# bldc_controller.net
KiCad netlist of a schematic drawn in EAGLE
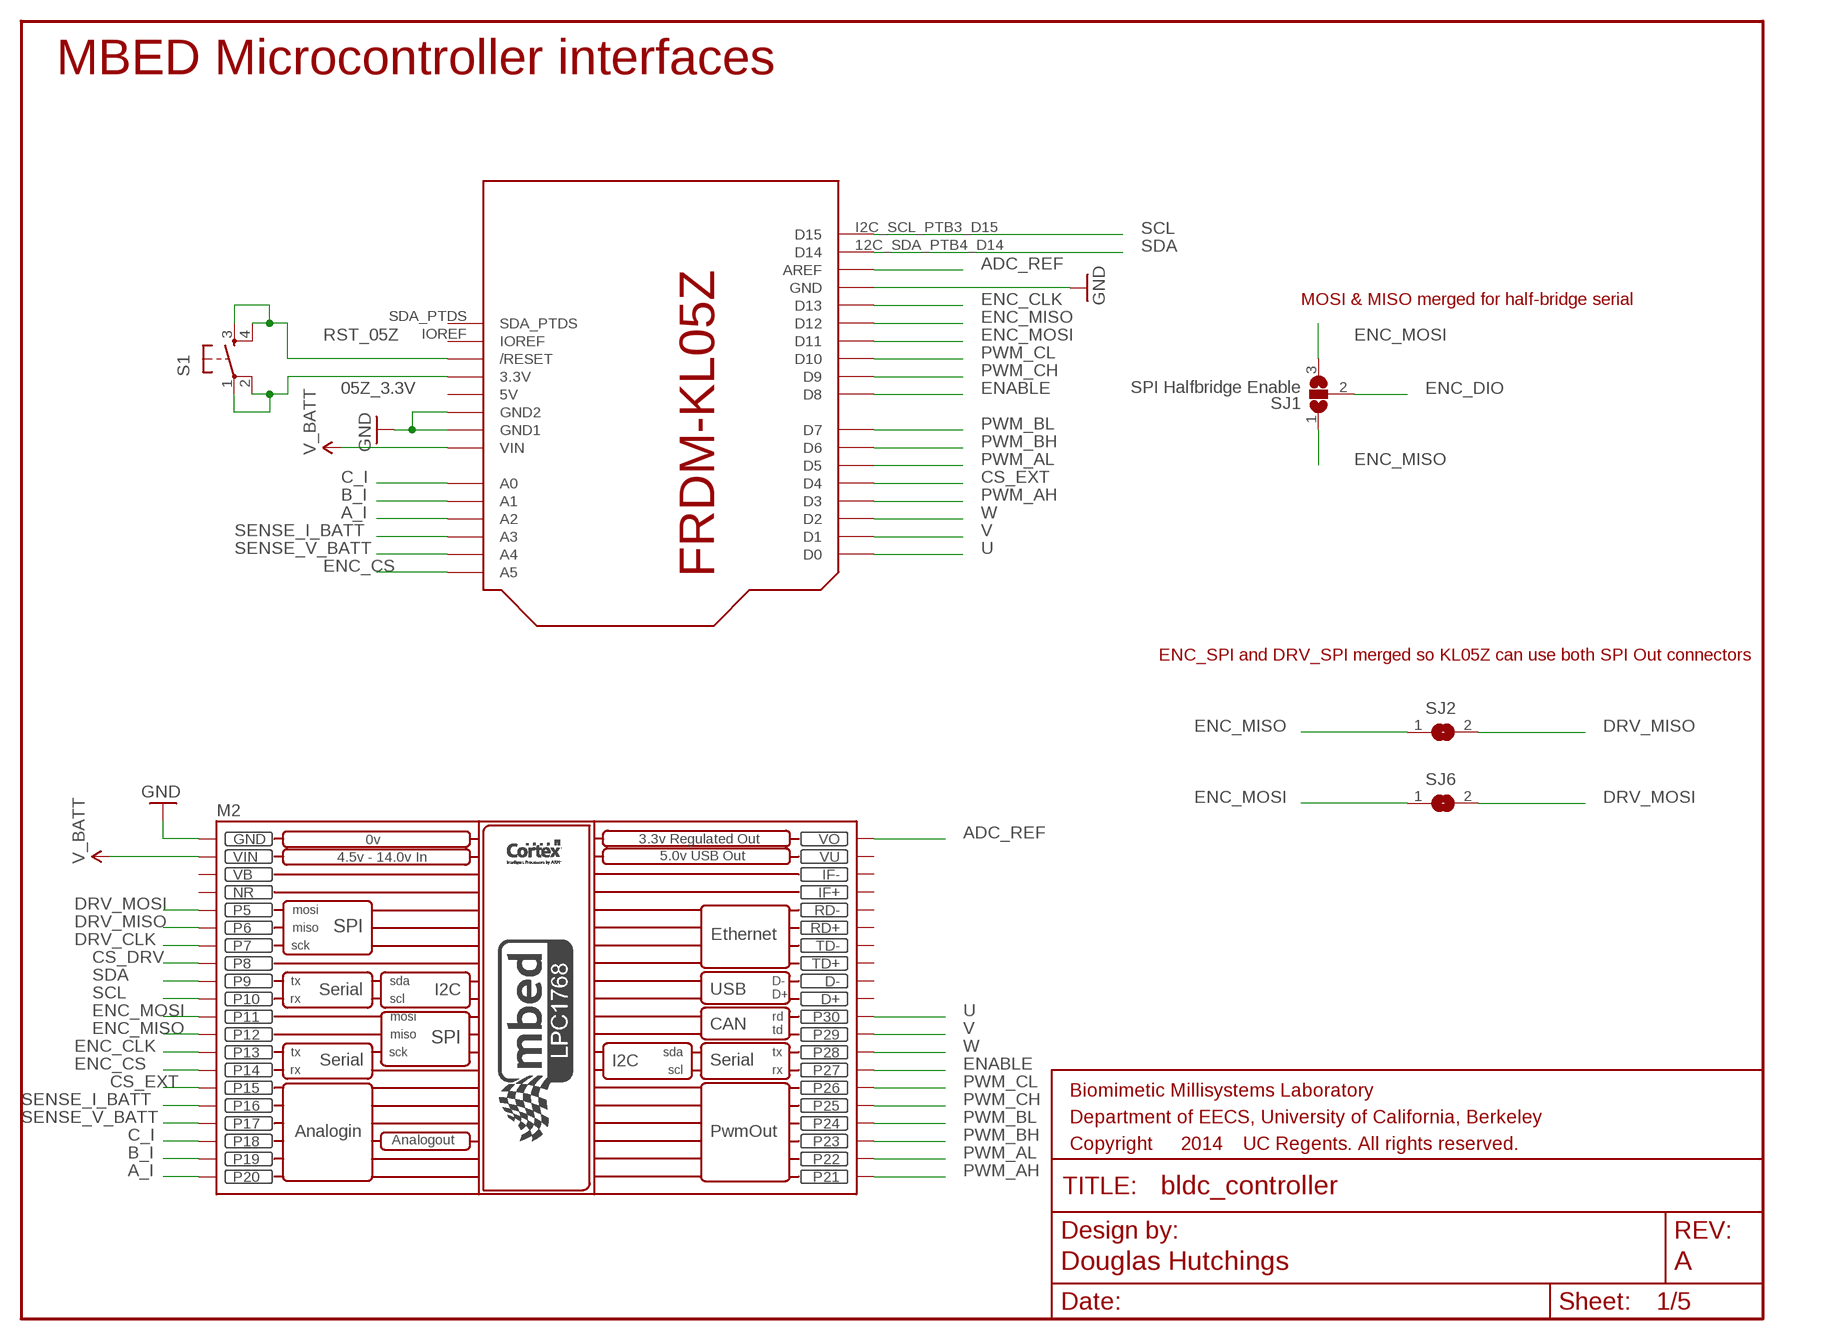
[diagram p0: schematic, sheet 1]
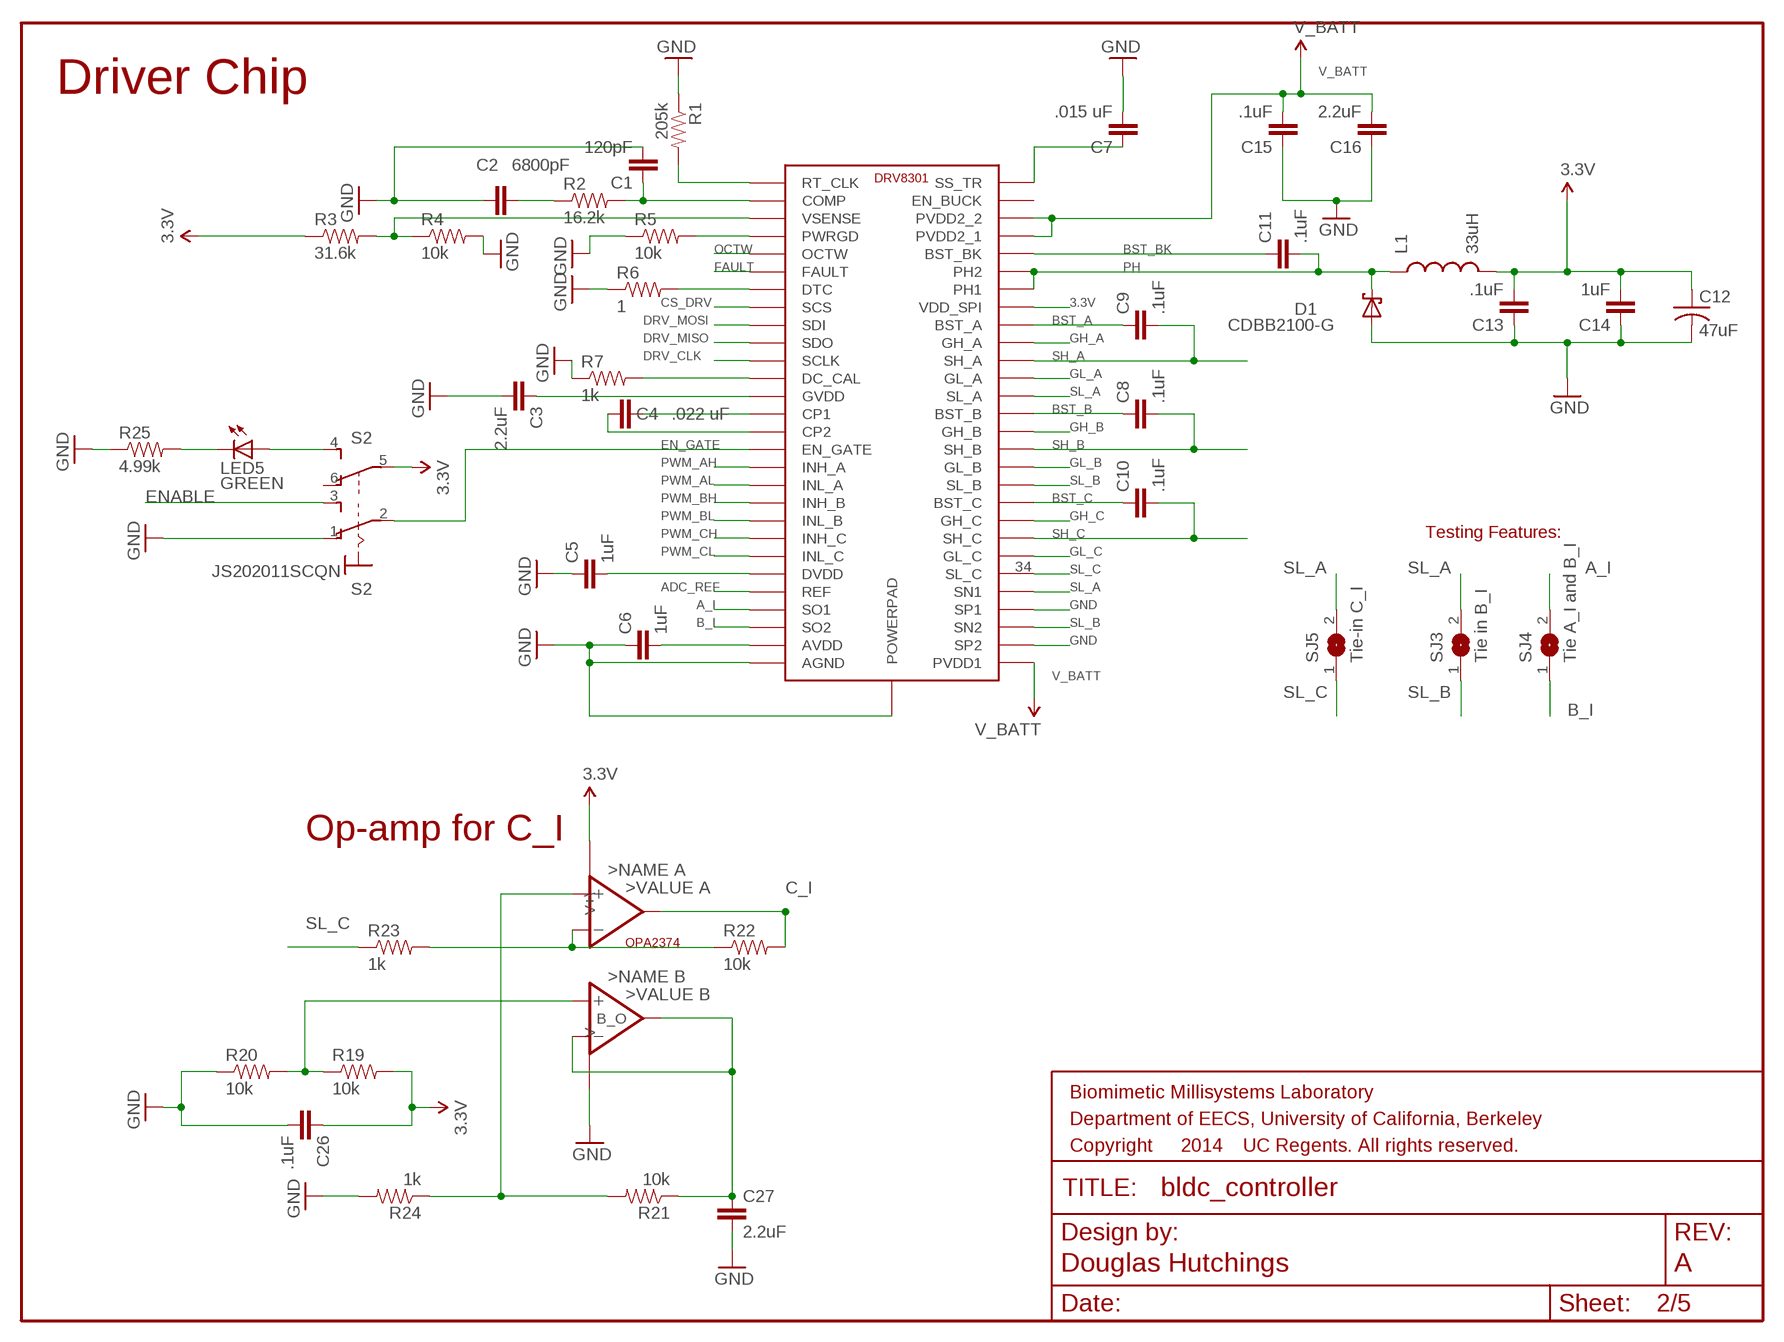
[diagram p1: schematic, sheet 2]
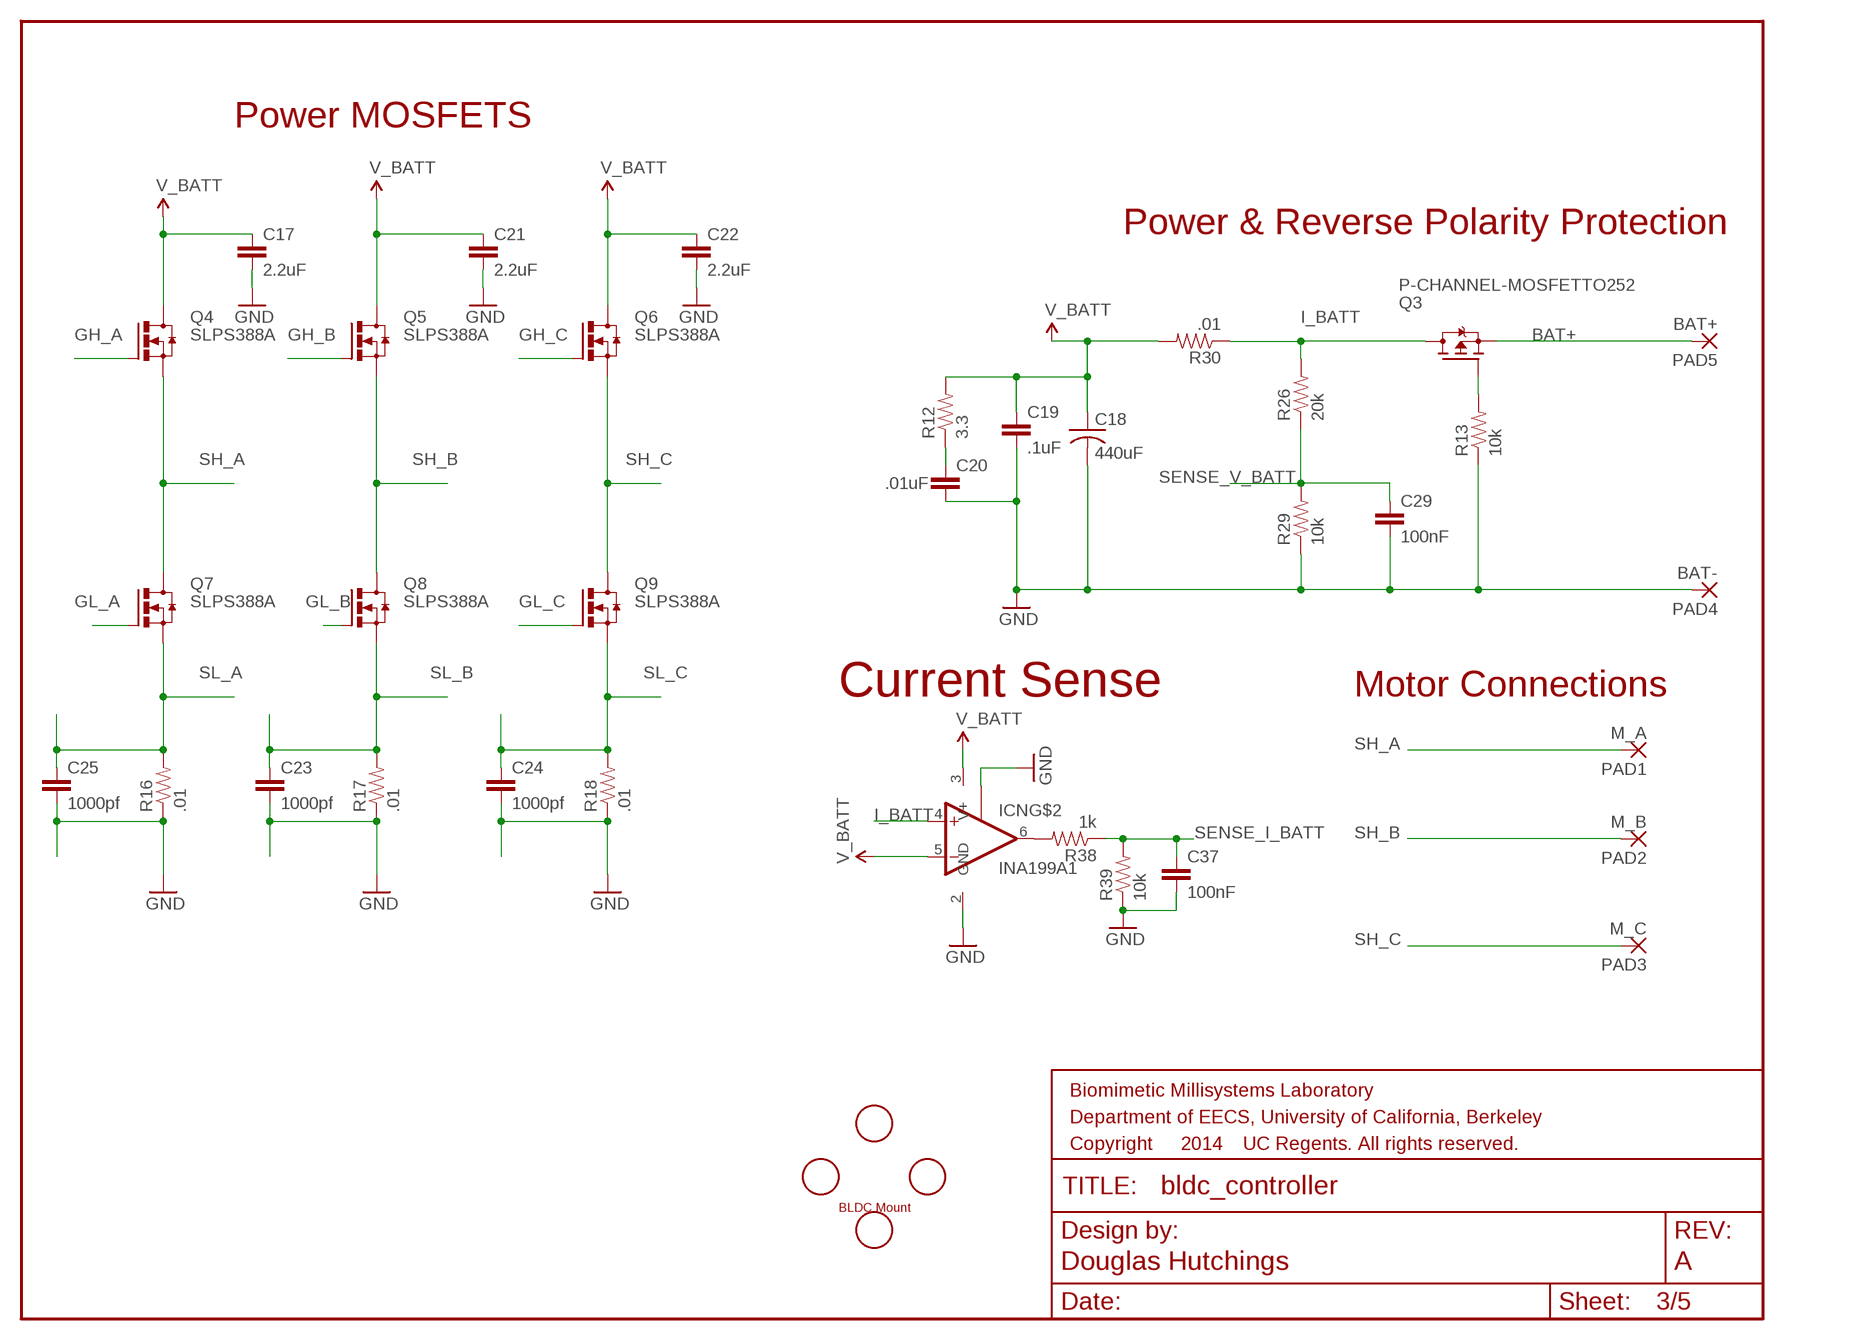
[diagram p2: schematic, sheet 3]
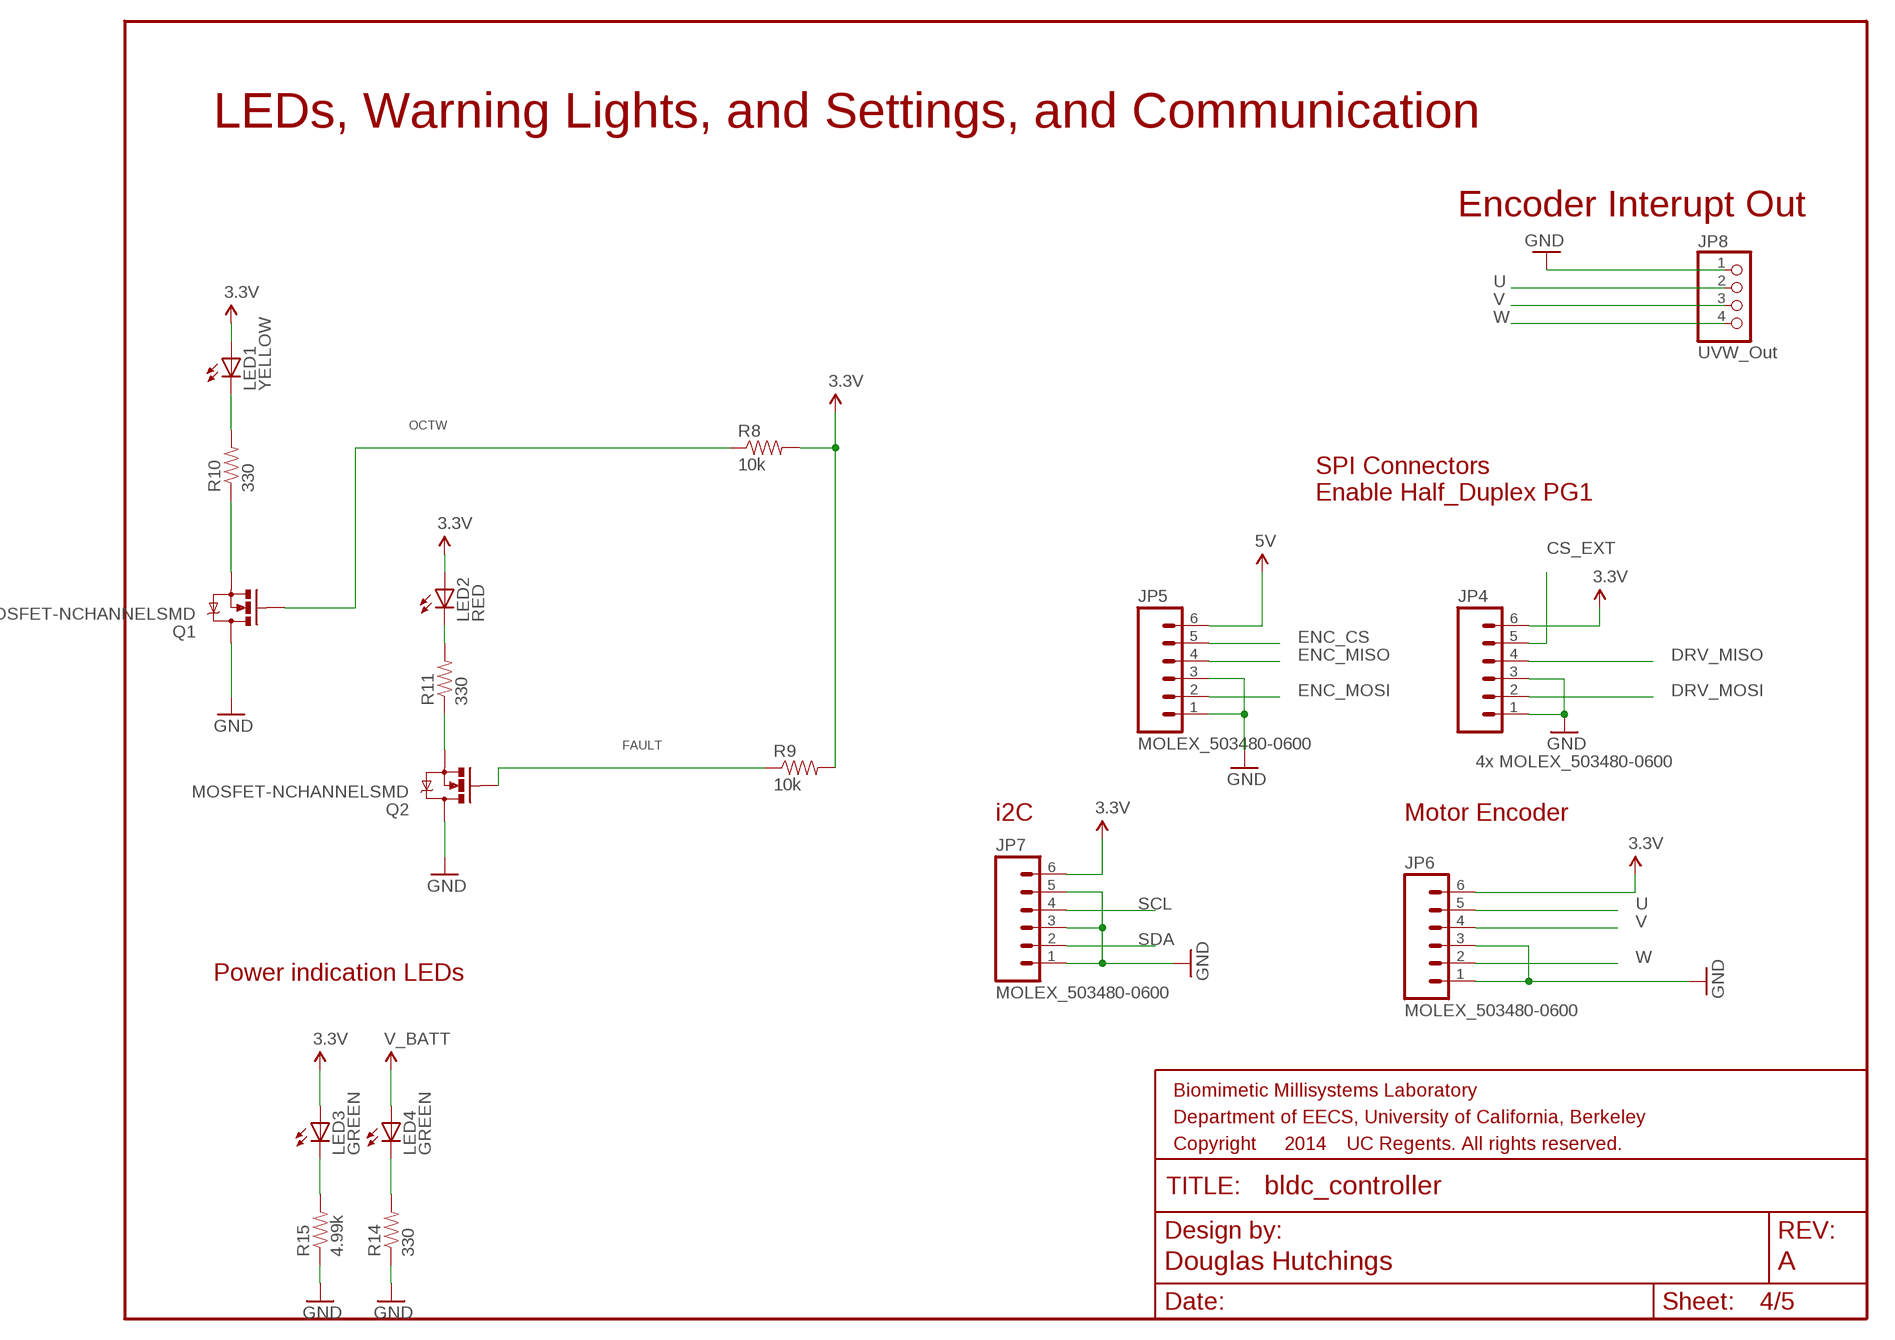
[diagram p3: schematic, sheet 4]
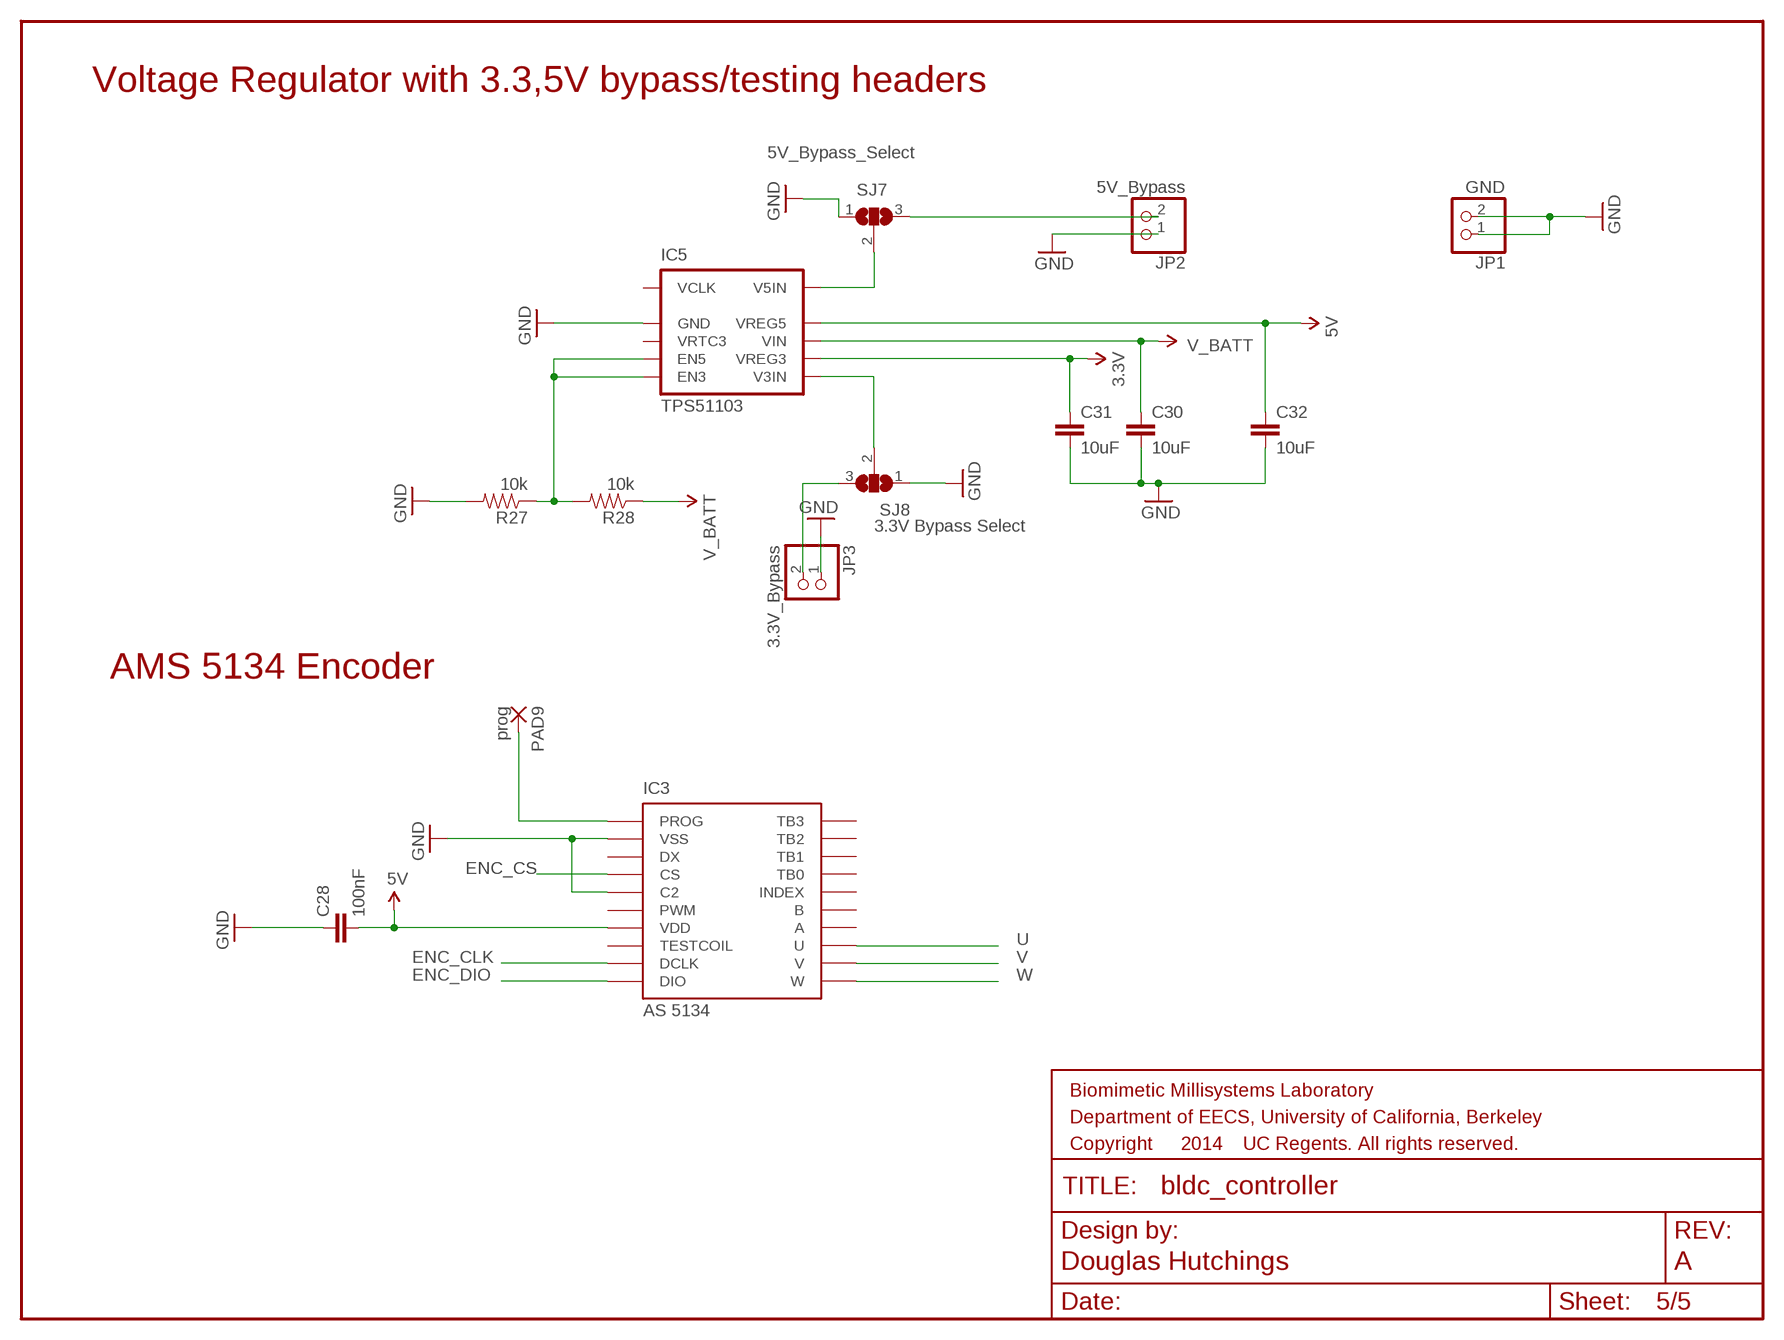
[diagram p4: schematic, sheet 5]

(export (version "E")
  (design (tool "Eeschema 10.0.6"))
  (components
    (comp (ref "JP4")
      (value "4x MOLEX_503480-0600")
      (footprint "eagle-import:MOLEX_503480-0600")
      (libsource (lib "eagle-import") (part "MOLEX_503480-0600"))
    )
    (comp (ref "JP5")
      (value "MOLEX_503480-0600")
      (footprint "eagle-import:MOLEX_503480-0600")
      (libsource (lib "eagle-import") (part "MOLEX_503480-0600"))
    )
    (comp (ref "JP6")
      (value "MOLEX_503480-0600")
      (footprint "eagle-import:MOLEX_503480-0600")
      (libsource (lib "eagle-import") (part "MOLEX_503480-0600"))
    )
    (comp (ref "JP7")
      (value "MOLEX_503480-0600")
      (footprint "eagle-import:MOLEX_503480-0600")
      (libsource (lib "eagle-import") (part "MOLEX_503480-0600"))
    )
    (comp (ref "JP8")
      (value "UVW_Out")
      (footprint "eagle-import:1X04")
      (libsource (lib "eagle-import") (part "PINHD-1X4"))
    )
    (comp (ref "LED1")
      (value "YELLOW")
      (footprint "eagle-import:LED-0603")
      (libsource (lib "eagle-import") (part "LED0603"))
    )
    (comp (ref "LED2")
      (value "RED")
      (footprint "eagle-import:LED-0603")
      (libsource (lib "eagle-import") (part "LED0603"))
    )
    (comp (ref "LED3")
      (value "GREEN")
      (footprint "eagle-import:LED-0603")
      (libsource (lib "eagle-import") (part "LED0603"))
    )
    (comp (ref "LED4")
      (value "GREEN")
      (footprint "eagle-import:LED-0603")
      (libsource (lib "eagle-import") (part "LED0603"))
    )
    (comp (ref "Q1")
      (value "MOSFET-NCHANNELSMD")
      (footprint "eagle-import:SOT23-3")
      (libsource (lib "eagle-import") (part "MOSFET-NCHANNELSMD"))
    )
    (comp (ref "Q2")
      (value "MOSFET-NCHANNELSMD")
      (footprint "eagle-import:SOT23-3")
      (libsource (lib "eagle-import") (part "MOSFET-NCHANNELSMD"))
    )
    (comp (ref "R8")
      (value "10k")
      (footprint "eagle-import:0402-RES")
      (libsource (lib "eagle-import") (part "RESISTOR0402-RES"))
    )
    (comp (ref "R9")
      (value "10k")
      (footprint "eagle-import:0402-RES")
      (libsource (lib "eagle-import") (part "RESISTOR0402-RES"))
    )
    (comp (ref "R10")
      (value "330")
      (footprint "eagle-import:0603-RES")
      (libsource (lib "eagle-import") (part "RESISTOR0603-RES"))
    )
    (comp (ref "R11")
      (value "330")
      (footprint "eagle-import:0603-RES")
      (libsource (lib "eagle-import") (part "RESISTOR0603-RES"))
    )
    (comp (ref "R14")
      (value "330")
      (footprint "eagle-import:0603-RES")
      (libsource (lib "eagle-import") (part "RESISTOR0603-RES"))
    )
    (comp (ref "R15")
      (value "4.99k")
      (footprint "eagle-import:0603-RES")
      (libsource (lib "eagle-import") (part "RESISTOR0603-RES"))
    )
    (comp (ref "C1")
      (value "120pF")
      (footprint "eagle-import:0402-CAP")
      (libsource (lib "eagle-import") (part "CAP0402-CAP"))
    )
    (comp (ref "C2")
      (value "6800pF")
      (footprint "eagle-import:0402-CAP")
      (libsource (lib "eagle-import") (part "CAP0402-CAP"))
    )
    (comp (ref "C3")
      (value "2.2uF")
      (footprint "eagle-import:0402-CAP")
      (libsource (lib "eagle-import") (part "CAP0402-CAP"))
    )
    (comp (ref "C4")
      (value ".022 uF")
      (footprint "eagle-import:0402-CAP")
      (libsource (lib "eagle-import") (part "CAP0402-CAP"))
    )
    (comp (ref "C5")
      (value "1uF")
      (footprint "eagle-import:0402-CAP")
      (libsource (lib "eagle-import") (part "CAP0402-CAP"))
    )
    (comp (ref "C6")
      (value "1uF")
      (footprint "eagle-import:0402-CAP")
      (libsource (lib "eagle-import") (part "CAP0402-CAP"))
    )
    (comp (ref "C7")
      (value ".015 uF")
      (footprint "eagle-import:0402-CAP")
      (libsource (lib "eagle-import") (part "CAP0402-CAP"))
    )
    (comp (ref "C8")
      (value ".1uF")
      (footprint "eagle-import:0402-CAP")
      (libsource (lib "eagle-import") (part "CAP0402-CAP"))
    )
    (comp (ref "C9")
      (value ".1uF")
      (footprint "eagle-import:0402-CAP")
      (libsource (lib "eagle-import") (part "CAP0402-CAP"))
    )
    (comp (ref "C10")
      (value ".1uF")
      (footprint "eagle-import:0402-CAP")
      (libsource (lib "eagle-import") (part "CAP0402-CAP"))
    )
    (comp (ref "C11")
      (value ".1uF")
      (footprint "eagle-import:0402-CAP")
      (libsource (lib "eagle-import") (part "CAP0402-CAP"))
    )
    (comp (ref "C12")
      (value "47uF")
      (footprint "eagle-import:C0603")
      (libsource (lib "eagle-import") (part "C-USC0603"))
    )
    (comp (ref "C13")
      (value ".1uF")
      (footprint "eagle-import:0402-CAP")
      (libsource (lib "eagle-import") (part "CAP0402-CAP"))
    )
    (comp (ref "C14")
      (value "1uF")
      (footprint "eagle-import:0402-CAP")
      (libsource (lib "eagle-import") (part "CAP0402-CAP"))
    )
    (comp (ref "C15")
      (value ".1uF")
      (footprint "eagle-import:0402-CAP")
      (libsource (lib "eagle-import") (part "CAP0402-CAP"))
    )
    (comp (ref "C16")
      (value "2.2uF")
      (footprint "eagle-import:0402-CAP")
      (libsource (lib "eagle-import") (part "CAP0402-CAP"))
    )
    (comp (ref "C26")
      (value ".1uF")
      (footprint "eagle-import:0402-CAP")
      (libsource (lib "eagle-import") (part "CAP0402-CAP"))
    )
    (comp (ref "C27")
      (value "2.2uF")
      (footprint "eagle-import:0402-CAP")
      (libsource (lib "eagle-import") (part "CAP0402-CAP"))
    )
    (comp (ref "D1")
      (value "CDBB2100-G")
      (footprint "eagle-import:SMB")
      (libsource (lib "eagle-import") (part "SCHOTTKY-DIODESMD"))
    )
    (comp (ref "IC1")
      (value "DRV8301")
      (footprint "eagle-import:DRV8301")
      (libsource (lib "eagle-import") (part "DRV8301"))
    )
    (comp (ref "IC2")
      (value "OPA2374")
      (footprint "eagle-import:SOT-23")
      (libsource (lib "eagle-import") (part "OPA2374"))
    )
    (comp (ref "L1")
      (value "33uH")
      (footprint "eagle-import:0805")
      (libsource (lib "eagle-import") (part "INDUCTOR0805"))
    )
    (comp (ref "LED5")
      (value "GREEN")
      (footprint "eagle-import:LED-0603")
      (libsource (lib "eagle-import") (part "LED0603"))
    )
    (comp (ref "R1")
      (value "205k")
      (footprint "eagle-import:0402-RES")
      (libsource (lib "eagle-import") (part "RESISTOR0402-RES"))
    )
    (comp (ref "R2")
      (value "16.2k")
      (footprint "eagle-import:0402-RES")
      (libsource (lib "eagle-import") (part "RESISTOR0402-RES"))
    )
    (comp (ref "R3")
      (value "31.6k")
      (footprint "eagle-import:0402-RES")
      (libsource (lib "eagle-import") (part "RESISTOR0402-RES"))
    )
    (comp (ref "R4")
      (value "10k")
      (footprint "eagle-import:0402-RES")
      (libsource (lib "eagle-import") (part "RESISTOR0402-RES"))
    )
    (comp (ref "R5")
      (value "10k")
      (footprint "eagle-import:0402-RES")
      (libsource (lib "eagle-import") (part "RESISTOR0402-RES"))
    )
    (comp (ref "R6")
      (value "1")
      (footprint "eagle-import:0402-RES")
      (libsource (lib "eagle-import") (part "RESISTOR0402-RES"))
    )
    (comp (ref "R7")
      (value "1k")
      (footprint "eagle-import:0402-RES")
      (libsource (lib "eagle-import") (part "RESISTOR0402-RES"))
    )
    (comp (ref "R19")
      (value "10k")
      (footprint "eagle-import:0402-RES")
      (libsource (lib "eagle-import") (part "RESISTOR0402-RES"))
    )
    (comp (ref "R20")
      (value "10k")
      (footprint "eagle-import:0402-RES")
      (libsource (lib "eagle-import") (part "RESISTOR0402-RES"))
    )
    (comp (ref "R21")
      (value "10k")
      (footprint "eagle-import:0402-RES")
      (libsource (lib "eagle-import") (part "RESISTOR0402-RES"))
    )
    (comp (ref "R22")
      (value "10k")
      (footprint "eagle-import:0402-RES")
      (libsource (lib "eagle-import") (part "RESISTOR0402-RES"))
    )
    (comp (ref "R23")
      (value "1k")
      (footprint "eagle-import:0402-RES")
      (libsource (lib "eagle-import") (part "RESISTOR0402-RES"))
    )
    (comp (ref "R24")
      (value "1k")
      (footprint "eagle-import:0402-RES")
      (libsource (lib "eagle-import") (part "RESISTOR0402-RES"))
    )
    (comp (ref "R25")
      (value "4.99k")
      (footprint "eagle-import:0603-RES")
      (libsource (lib "eagle-import") (part "RESISTOR0603-RES"))
    )
    (comp (ref "S2")
      (value "JS202011SCQN")
      (footprint "eagle-import:JS202011SCQN")
      (libsource (lib "eagle-import") (part "JS202011SCQN"))
    )
    (comp (ref "SJ3")
      (value "Tie in B_I")
      (footprint "eagle-import:SJ")
      (libsource (lib "eagle-import") (part "SJ"))
    )
    (comp (ref "SJ4")
      (value "Tie A_I and B_I")
      (footprint "eagle-import:SJ")
      (libsource (lib "eagle-import") (part "SJ"))
    )
    (comp (ref "SJ5")
      (value "Tie-in C_I")
      (footprint "eagle-import:SJ")
      (libsource (lib "eagle-import") (part "SJ"))
    )
    (comp (ref "C28")
      (value "100nF")
      (footprint "eagle-import:0402-CAP")
      (libsource (lib "eagle-import") (part "CAP0402-CAP"))
    )
    (comp (ref "C30")
      (value "10uF")
      (footprint "eagle-import:0603-CAP")
      (libsource (lib "eagle-import") (part "CAP0603-CAP"))
    )
    (comp (ref "C31")
      (value "10uF")
      (footprint "eagle-import:0603-CAP")
      (libsource (lib "eagle-import") (part "CAP0603-CAP"))
    )
    (comp (ref "C32")
      (value "10uF")
      (footprint "eagle-import:0603-CAP")
      (libsource (lib "eagle-import") (part "CAP0603-CAP"))
    )
    (comp (ref "IC3")
      (value "AS 5134")
      (footprint "eagle-import:AS5134")
      (libsource (lib "eagle-import") (part "AS5134"))
    )
    (comp (ref "IC5")
      (value "TPS51103")
      (footprint "eagle-import:DRC(S-PVSON-N10)")
      (libsource (lib "eagle-import") (part "TPS51103"))
    )
    (comp (ref "JP1")
      (value "GND")
      (footprint "eagle-import:1X02")
      (libsource (lib "eagle-import") (part "PINHD-1X2"))
    )
    (comp (ref "JP2")
      (value "5V_Bypass")
      (footprint "eagle-import:1X02")
      (libsource (lib "eagle-import") (part "PINHD-1X2"))
    )
    (comp (ref "JP3")
      (value "3.3V_Bypass")
      (footprint "eagle-import:1X02")
      (libsource (lib "eagle-import") (part "PINHD-1X2"))
    )
    (comp (ref "PAD9")
      (value "prog")
      (footprint "eagle-import:SMD1,27-2,54")
      (libsource (lib "eagle-import") (part "SMD2"))
    )
    (comp (ref "R27")
      (value "10k")
      (footprint "eagle-import:0402-RES")
      (libsource (lib "eagle-import") (part "RESISTOR0402-RES"))
    )
    (comp (ref "R28")
      (value "10k")
      (footprint "eagle-import:0402-RES")
      (libsource (lib "eagle-import") (part "RESISTOR0402-RES"))
    )
    (comp (ref "SJ7")
      (value "5V_Bypass_Select")
      (footprint "eagle-import:SJ_2")
      (libsource (lib "eagle-import") (part "SJ2W"))
    )
    (comp (ref "SJ8")
      (value "3.3V Bypass Select")
      (footprint "eagle-import:SJ_2")
      (libsource (lib "eagle-import") (part "SJ2W"))
    )
    (comp (ref "C17")
      (value "2.2uF")
      (footprint "eagle-import:0603-CAP")
      (libsource (lib "eagle-import") (part "CAP0603-CAP"))
    )
    (comp (ref "C18")
      (value "440uF")
      (footprint "eagle-import:C1210")
      (libsource (lib "eagle-import") (part "C-USC1210"))
    )
    (comp (ref "C19")
      (value ".1uF")
      (footprint "eagle-import:0402-CAP")
      (libsource (lib "eagle-import") (part "CAP0402-CAP"))
    )
    (comp (ref "C20")
      (value ".01uF")
      (footprint "eagle-import:0402-CAP")
      (libsource (lib "eagle-import") (part "CAP0402-CAP"))
    )
    (comp (ref "C21")
      (value "2.2uF")
      (footprint "eagle-import:0603-CAP")
      (libsource (lib "eagle-import") (part "CAP0603-CAP"))
    )
    (comp (ref "C22")
      (value "2.2uF")
      (footprint "eagle-import:0603-CAP")
      (libsource (lib "eagle-import") (part "CAP0603-CAP"))
    )
    (comp (ref "C23")
      (value "1000pf")
      (footprint "eagle-import:0603-CAP")
      (libsource (lib "eagle-import") (part "CAP0603-CAP"))
    )
    (comp (ref "C24")
      (value "1000pf")
      (footprint "eagle-import:0603-CAP")
      (libsource (lib "eagle-import") (part "CAP0603-CAP"))
    )
    (comp (ref "C25")
      (value "1000pf")
      (footprint "eagle-import:0603-CAP")
      (libsource (lib "eagle-import") (part "CAP0603-CAP"))
    )
    (comp (ref "C29")
      (value "100nF")
      (footprint "eagle-import:0402-CAP")
      (libsource (lib "eagle-import") (part "CAP0402-CAP"))
    )
    (comp (ref "C37")
      (value "100nF")
      (footprint "eagle-import:0402-CAP")
      (libsource (lib "eagle-import") (part "CAP0402-CAP"))
    )
    (comp (ref "ICN")
      (value "INA199A1")
      (footprint "eagle-import:SC70-6")
      (libsource (lib "eagle-import") (part "INA199A1"))
    )
    (comp (ref "PAD1")
      (value "M_A")
      (footprint "eagle-import:SMD1,27-2,54")
      (libsource (lib "eagle-import") (part "SMD2"))
    )
    (comp (ref "PAD2")
      (value "M_B")
      (footprint "eagle-import:SMD1,27-2,54")
      (libsource (lib "eagle-import") (part "SMD2"))
    )
    (comp (ref "PAD3")
      (value "M_C")
      (footprint "eagle-import:SMD1,27-2,54")
      (libsource (lib "eagle-import") (part "SMD2"))
    )
    (comp (ref "PAD4")
      (value "BAT-")
      (footprint "eagle-import:SMD1,27-2,54")
      (libsource (lib "eagle-import") (part "SMD2"))
    )
    (comp (ref "PAD5")
      (value "BAT+")
      (footprint "eagle-import:SMD1,27-2,54")
      (libsource (lib "eagle-import") (part "SMD2"))
    )
    (comp (ref "Q3")
      (value "P-CHANNEL-MOSFETTO252")
      (footprint "eagle-import:TO252")
      (libsource (lib "eagle-import") (part "P-CHANNEL-MOSFETTO252"))
    )
    (comp (ref "Q4")
      (value "SLPS388A")
      (footprint "eagle-import:SLPS388A")
      (libsource (lib "eagle-import") (part "SLPS388A"))
    )
    (comp (ref "Q5")
      (value "SLPS388A")
      (footprint "eagle-import:SLPS388A")
      (libsource (lib "eagle-import") (part "SLPS388A"))
    )
    (comp (ref "Q6")
      (value "SLPS388A")
      (footprint "eagle-import:SLPS388A")
      (libsource (lib "eagle-import") (part "SLPS388A"))
    )
    (comp (ref "Q7")
      (value "SLPS388A")
      (footprint "eagle-import:SLPS388A")
      (libsource (lib "eagle-import") (part "SLPS388A"))
    )
    (comp (ref "Q8")
      (value "SLPS388A")
      (footprint "eagle-import:SLPS388A")
      (libsource (lib "eagle-import") (part "SLPS388A"))
    )
    (comp (ref "Q9")
      (value "SLPS388A")
      (footprint "eagle-import:SLPS388A")
      (libsource (lib "eagle-import") (part "SLPS388A"))
    )
    (comp (ref "R12")
      (value "3.3")
      (footprint "eagle-import:0402-RES")
      (libsource (lib "eagle-import") (part "RESISTOR0402-RES"))
    )
    (comp (ref "R13")
      (value "10k")
      (footprint "eagle-import:0603-RES")
      (libsource (lib "eagle-import") (part "RESISTOR0603-RES"))
    )
    (comp (ref "R16")
      (value ".01")
      (footprint "eagle-import:R2010")
      (libsource (lib "eagle-import") (part "RESISTOR2010"))
    )
    (comp (ref "R17")
      (value ".01")
      (footprint "eagle-import:R2010")
      (libsource (lib "eagle-import") (part "RESISTOR2010"))
    )
    (comp (ref "R18")
      (value ".01")
      (footprint "eagle-import:R2010")
      (libsource (lib "eagle-import") (part "RESISTOR2010"))
    )
    (comp (ref "R26")
      (value "20k")
      (footprint "eagle-import:0402-RES")
      (libsource (lib "eagle-import") (part "RESISTOR0402-RES"))
    )
    (comp (ref "R29")
      (value "10k")
      (footprint "eagle-import:0402-RES")
      (libsource (lib "eagle-import") (part "RESISTOR0402-RES"))
    )
    (comp (ref "R30")
      (value ".01")
      (footprint "eagle-import:R2010")
      (libsource (lib "eagle-import") (part "RESISTOR2010"))
    )
    (comp (ref "R38")
      (value "1k")
      (footprint "eagle-import:0402-RES")
      (libsource (lib "eagle-import") (part "RESISTOR0402-RES"))
    )
    (comp (ref "R39")
      (value "10k")
      (footprint "eagle-import:0402-RES")
      (libsource (lib "eagle-import") (part "RESISTOR0402-RES"))
    )
    (comp (ref "U$8")
      (value "BLDC_MOUNT")
      (footprint "eagle-import:BLDC_MOUNT")
      (libsource (lib "eagle-import") (part "BLDC_MOUNT"))
    )
    (comp (ref "M1")
      (value "FRDM-KL05Z")
      (footprint "eagle-import:FREESCALEKL05Z")
      (libsource (lib "eagle-import") (part "FRDM-KL05Z"))
    )
    (comp (ref "M2")
      (value "MBED_NXP_LPC1768")
      (footprint "eagle-import:MBED-KIT")
      (libsource (lib "eagle-import") (part "MBED_NXP_LPC1768"))
    )
    (comp (ref "S1")
      (value "TAC_SWITCHPTH")
      (footprint "eagle-import:TACTILE-PTH")
      (libsource (lib "eagle-import") (part "TAC_SWITCHPTH"))
    )
    (comp (ref "SJ1")
      (value "SPI Halfbridge Enable")
      (footprint "eagle-import:SJ_2")
      (libsource (lib "eagle-import") (part "SJ2W"))
    )
    (comp (ref "SJ2") (value "SJ") (footprint "eagle-import:SJ") (libsource (lib "eagle-import") (part "SJ")))
    (comp (ref "SJ6") (value "SJ") (footprint "eagle-import:SJ") (libsource (lib "eagle-import") (part "SJ")))
  )
  (nets
    (net (code "1") (name "3.3V") (class "Default")
      (node (ref "C12") (pin "1") (pinfunction "1_1") (pintype "passive"))
      (node (ref "C13") (pin "2") (pinfunction "2_2") (pintype "passive"))
      (node (ref "C14") (pin "2") (pinfunction "2_2") (pintype "passive"))
      (node (ref "C26") (pin "1") (pinfunction "1_1") (pintype "passive"))
      (node (ref "C31") (pin "1") (pinfunction "1_1") (pintype "passive"))
      (node (ref "IC1") (pin "49") (pinfunction "VDD_SPI_49") (pintype "bidirectional"))
      (node (ref "IC2") (pin "5") (pinfunction "V+\\_5") (pintype "bidirectional"))
      (node (ref "IC5") (pin "7") (pinfunction "VREG3_7") (pintype "input"))
      (node (ref "JP4") (pin "6") (pinfunction "6_6") (pintype "passive"))
      (node (ref "JP6") (pin "6") (pinfunction "6_6") (pintype "passive"))
      (node (ref "JP7") (pin "6") (pinfunction "6_6") (pintype "passive"))
      (node (ref "L1") (pin "2") (pinfunction "2_2") (pintype "passive"))
      (node (ref "LED1") (pin "A") (pinfunction "A_A") (pintype "passive"))
      (node (ref "LED2") (pin "A") (pinfunction "A_A") (pintype "passive"))
      (node (ref "LED3") (pin "A") (pinfunction "A_A") (pintype "passive"))
      (node (ref "R19") (pin "2") (pinfunction "2_2") (pintype "passive"))
      (node (ref "R3") (pin "1") (pinfunction "1_1") (pintype "passive"))
      (node (ref "R8") (pin "2") (pinfunction "2_2") (pintype "passive"))
      (node (ref "R9") (pin "2") (pinfunction "2_2") (pintype "passive"))
      (node (ref "S2") (pin "5") (pinfunction "P_5") (pintype "passive"))
    )
    (net (code "2") (name "5V") (class "Default")
      (node (ref "C28") (pin "2") (pinfunction "2_2") (pintype "passive"))
      (node (ref "C32") (pin "1") (pinfunction "1_1") (pintype "passive"))
      (node (ref "IC3") (pin "7") (pinfunction "VDD_7") (pintype "power_in"))
      (node (ref "IC5") (pin "9") (pinfunction "VREG5_9") (pintype "input"))
      (node (ref "JP5") (pin "6") (pinfunction "6_6") (pintype "passive"))
    )
    (net (code "3") (name "05Z_3.3V") (class "Default")
      (node (ref "M1") (pin "3.3V") (pinfunction "3.3V_3.3V") (pintype "output"))
      (node (ref "S1") (pin "1") (pinfunction "1_1") (pintype "passive"))
      (node (ref "S1") (pin "2") (pinfunction "2_2") (pintype "passive"))
    )
    (net (code "4") (name "ADC_REF") (class "Default")
      (node (ref "IC1") (pin "24") (pinfunction "REF_24") (pintype "bidirectional"))
      (node (ref "M1") (pin "AVDD") (pinfunction "AREF_AVDD") (pintype "bidirectional"))
      (node (ref "M2") (pin "VOUT") (pinfunction "VO_VOUT") (pintype "output"))
    )
    (net (code "5") (name "A_I") (class "Default")
      (node (ref "IC1") (pin "25") (pinfunction "SO1_25") (pintype "bidirectional"))
      (node (ref "M1") (pin "A2_PTA8") (pinfunction "A2_A2_PTA8") (pintype "bidirectional"))
      (node (ref "M2") (pin "P$20") (pinfunction "P20_P$20") (pintype "bidirectional"))
      (node (ref "SJ4") (pin "2") (pinfunction "2_2") (pintype "passive"))
    )
    (net (code "6") (name "BAT+") (class "Default")
      (node (ref "PAD5") (pin "1") (pinfunction "P_1") (pintype "passive"))
      (node (ref "Q3") (pin "2") (pinfunction "S_2") (pintype "passive"))
    )
    (net (code "7") (name "BST_A") (class "Default")
      (node (ref "C9") (pin "1") (pinfunction "1_1") (pintype "passive"))
      (node (ref "IC1") (pin "48") (pinfunction "BST_A_48") (pintype "bidirectional"))
    )
    (net (code "8") (name "BST_B") (class "Default")
      (node (ref "C8") (pin "1") (pinfunction "1_1") (pintype "passive"))
      (node (ref "IC1") (pin "43") (pinfunction "BST_B_43") (pintype "bidirectional"))
    )
    (net (code "9") (name "BST_BK") (class "Default")
      (node (ref "C11") (pin "1") (pinfunction "1_1") (pintype "passive"))
      (node (ref "IC1") (pin "52") (pinfunction "BST_BK_52") (pintype "bidirectional"))
    )
    (net (code "10") (name "BST_C") (class "Default")
      (node (ref "C10") (pin "1") (pinfunction "1_1") (pintype "passive"))
      (node (ref "IC1") (pin "38") (pinfunction "BST_C_38") (pintype "bidirectional"))
    )
    (net (code "11") (name "B_I") (class "Default")
      (node (ref "IC1") (pin "26") (pinfunction "SO2_26") (pintype "bidirectional"))
      (node (ref "M1") (pin "A1_PTB9") (pinfunction "A1_A1_PTB9") (pintype "bidirectional"))
      (node (ref "M2") (pin "P$19") (pinfunction "P19_P$19") (pintype "bidirectional"))
      (node (ref "SJ4") (pin "1") (pinfunction "1_1") (pintype "passive"))
    )
    (net (code "12") (name "CS_DRV") (class "Default")
      (node (ref "IC1") (pin "8") (pinfunction "SCS_8") (pintype "bidirectional"))
      (node (ref "M2") (pin "P$8") (pinfunction "P8_P$8") (pintype "bidirectional"))
    )
    (net (code "13") (name "CS_EXT") (class "Default")
      (node (ref "JP4") (pin "5") (pinfunction "5_5") (pintype "passive"))
      (node (ref "M1") (pin "PTA10_D4") (pinfunction "D4_PTA10_D4") (pintype "bidirectional"))
      (node (ref "M2") (pin "P$15") (pinfunction "P15_P$15") (pintype "bidirectional"))
    )
    (net (code "14") (name "C_I") (class "Default")
      (node (ref "IC2") (pin "1") (pinfunction "A_O_1") (pintype "bidirectional"))
      (node (ref "M1") (pin "A0_PTB8") (pinfunction "A0_A0_PTB8") (pintype "bidirectional"))
      (node (ref "M2") (pin "P$18") (pinfunction "P18_P$18") (pintype "bidirectional"))
      (node (ref "R22") (pin "2") (pinfunction "2_2") (pintype "passive"))
    )
    (net (code "15") (name "DRV_CLK") (class "Default")
      (node (ref "IC1") (pin "11") (pinfunction "SCLK_11") (pintype "bidirectional"))
      (node (ref "M2") (pin "P$7") (pinfunction "P7_P$7") (pintype "bidirectional"))
    )
    (net (code "16") (name "DRV_MISO") (class "Default")
      (node (ref "IC1") (pin "10") (pinfunction "SDO_10") (pintype "bidirectional"))
      (node (ref "JP4") (pin "4") (pinfunction "4_4") (pintype "passive"))
      (node (ref "M2") (pin "P$6") (pinfunction "P6_P$6") (pintype "bidirectional"))
      (node (ref "SJ2") (pin "2") (pinfunction "2_2") (pintype "passive"))
    )
    (net (code "17") (name "DRV_MOSI") (class "Default")
      (node (ref "IC1") (pin "9") (pinfunction "SDI_9") (pintype "bidirectional"))
      (node (ref "JP4") (pin "2") (pinfunction "2_2") (pintype "passive"))
      (node (ref "M2") (pin "P$5") (pinfunction "P5_P$5") (pintype "bidirectional"))
      (node (ref "SJ6") (pin "2") (pinfunction "2_2") (pintype "passive"))
    )
    (net (code "18") (name "ENABLE") (class "Default")
      (node (ref "M1") (pin "PTB10_D8") (pinfunction "D8_PTB10_D8") (pintype "bidirectional"))
      (node (ref "M2") (pin "P$27") (pinfunction "P27_P$27") (pintype "bidirectional"))
      (node (ref "S2") (pin "3") (pinfunction "S_3") (pintype "passive"))
    )
    (net (code "19") (name "ENC_CLK") (class "Default")
      (node (ref "IC3") (pin "9") (pinfunction "DCLK_9") (pintype "input"))
      (node (ref "M1") (pin "SCK_PTB0_D13") (pinfunction "D13_SCK_PTB0_D13") (pintype "bidirectional"))
      (node (ref "M2") (pin "P$13") (pinfunction "P13_P$13") (pintype "bidirectional"))
    )
    (net (code "20") (name "ENC_CS") (class "Default")
      (node (ref "IC3") (pin "4") (pinfunction "CS_4") (pintype "input"))
      (node (ref "JP5") (pin "5") (pinfunction "5_5") (pintype "passive"))
      (node (ref "M1") (pin "A5_PTB13") (pinfunction "A5_A5_PTB13") (pintype "bidirectional"))
      (node (ref "M2") (pin "P$14") (pinfunction "P14_P$14") (pintype "bidirectional"))
    )
    (net (code "21") (name "ENC_DIO") (class "Default")
      (node (ref "IC3") (pin "10") (pinfunction "DIO_10") (pintype "bidirectional"))
      (node (ref "SJ1") (pin "2") (pinfunction "2_2") (pintype "passive"))
    )
    (net (code "22") (name "ENC_MISO") (class "Default")
      (node (ref "JP5") (pin "4") (pinfunction "4_4") (pintype "passive"))
      (node (ref "M1") (pin "MISO_PTA6_D12") (pinfunction "D12_MISO_PTA6_D12") (pintype "bidirectional"))
      (node (ref "M2") (pin "P$12") (pinfunction "P12_P$12") (pintype "bidirectional"))
      (node (ref "SJ1") (pin "1") (pinfunction "1_1") (pintype "passive"))
      (node (ref "SJ2") (pin "1") (pinfunction "1_1") (pintype "passive"))
    )
    (net (code "23") (name "ENC_MOSI") (class "Default")
      (node (ref "JP5") (pin "2") (pinfunction "2_2") (pintype "passive"))
      (node (ref "M1") (pin "MOSI_PTA_D11") (pinfunction "D11_MOSI_PTA_D11") (pintype "bidirectional"))
      (node (ref "M2") (pin "P$11") (pinfunction "P11_P$11") (pintype "bidirectional"))
      (node (ref "SJ1") (pin "3") (pinfunction "3_3") (pintype "passive"))
      (node (ref "SJ6") (pin "1") (pinfunction "1_1") (pintype "passive"))
    )
    (net (code "24") (name "EN_GATE") (class "Default")
      (node (ref "IC1") (pin "16") (pinfunction "EN_GATE_16") (pintype "bidirectional"))
      (node (ref "S2") (pin "2") (pinfunction "P_2") (pintype "passive"))
    )
    (net (code "25") (name "FAULT") (class "Default")
      (node (ref "IC1") (pin "6") (pinfunction "FAULT_6") (pintype "bidirectional"))
      (node (ref "Q2") (pin "1") (pinfunction "G_1") (pintype "passive"))
      (node (ref "R9") (pin "1") (pinfunction "1_1") (pintype "passive"))
    )
    (net (code "26") (name "GH_A") (class "Default")
      (node (ref "IC1") (pin "47") (pinfunction "GH_A_47") (pintype "bidirectional"))
      (node (ref "Q4") (pin "4") (pinfunction "G_4") (pintype "passive"))
    )
    (net (code "27") (name "GH_B") (class "Default")
      (node (ref "IC1") (pin "42") (pinfunction "GH_B_42") (pintype "bidirectional"))
      (node (ref "Q5") (pin "4") (pinfunction "G_4") (pintype "passive"))
    )
    (net (code "28") (name "GH_C") (class "Default")
      (node (ref "IC1") (pin "37") (pinfunction "GH_C_37") (pintype "bidirectional"))
      (node (ref "Q6") (pin "4") (pinfunction "G_4") (pintype "passive"))
    )
    (net (code "29") (name "GL_A") (class "Default")
      (node (ref "IC1") (pin "45") (pinfunction "GL_A_45") (pintype "bidirectional"))
      (node (ref "Q7") (pin "4") (pinfunction "G_4") (pintype "passive"))
    )
    (net (code "30") (name "GL_B") (class "Default")
      (node (ref "IC1") (pin "40") (pinfunction "GL_B_40") (pintype "bidirectional"))
      (node (ref "Q8") (pin "4") (pinfunction "G_4") (pintype "passive"))
    )
    (net (code "31") (name "GL_C") (class "Default")
      (node (ref "IC1") (pin "35") (pinfunction "GL_C_35") (pintype "bidirectional"))
      (node (ref "Q9") (pin "4") (pinfunction "G_4") (pintype "passive"))
    )
    (net (code "32") (name "GND") (class "Default")
      (node (ref "C1") (pin "2") (pinfunction "2_2") (pintype "passive"))
      (node (ref "C12") (pin "2") (pinfunction "2_2") (pintype "passive"))
      (node (ref "C13") (pin "1") (pinfunction "1_1") (pintype "passive"))
      (node (ref "C14") (pin "1") (pinfunction "1_1") (pintype "passive"))
      (node (ref "C15") (pin "1") (pinfunction "1_1") (pintype "passive"))
      (node (ref "C16") (pin "1") (pinfunction "1_1") (pintype "passive"))
      (node (ref "C17") (pin "2") (pinfunction "2_2") (pintype "passive"))
      (node (ref "C18") (pin "2") (pinfunction "2_2") (pintype "passive"))
      (node (ref "C19") (pin "2") (pinfunction "2_2") (pintype "passive"))
      (node (ref "C2") (pin "2") (pinfunction "2_2") (pintype "passive"))
      (node (ref "C20") (pin "2") (pinfunction "2_2") (pintype "passive"))
      (node (ref "C21") (pin "2") (pinfunction "2_2") (pintype "passive"))
      (node (ref "C22") (pin "2") (pinfunction "2_2") (pintype "passive"))
      (node (ref "C23") (pin "2") (pinfunction "2_2") (pintype "passive"))
      (node (ref "C24") (pin "2") (pinfunction "2_2") (pintype "passive"))
      (node (ref "C25") (pin "2") (pinfunction "2_2") (pintype "passive"))
      (node (ref "C26") (pin "2") (pinfunction "2_2") (pintype "passive"))
      (node (ref "C27") (pin "2") (pinfunction "2_2") (pintype "passive"))
      (node (ref "C28") (pin "1") (pinfunction "1_1") (pintype "passive"))
      (node (ref "C29") (pin "2") (pinfunction "2_2") (pintype "passive"))
      (node (ref "C3") (pin "2") (pinfunction "2_2") (pintype "passive"))
      (node (ref "C30") (pin "2") (pinfunction "2_2") (pintype "passive"))
      (node (ref "C31") (pin "2") (pinfunction "2_2") (pintype "passive"))
      (node (ref "C32") (pin "2") (pinfunction "2_2") (pintype "passive"))
      (node (ref "C37") (pin "2") (pinfunction "2_2") (pintype "passive"))
      (node (ref "C5") (pin "1") (pinfunction "1_1") (pintype "passive"))
      (node (ref "C6") (pin "1") (pinfunction "1_1") (pintype "passive"))
      (node (ref "C7") (pin "2") (pinfunction "2_2") (pintype "passive"))
      (node (ref "D1") (pin "A") (pinfunction "A_A") (pintype "passive"))
      (node (ref "IC1") (pin "28") (pinfunction "AGND_28") (pintype "bidirectional"))
      (node (ref "IC1") (pin "30") (pinfunction "SP2_30") (pintype "bidirectional"))
      (node (ref "IC1") (pin "32") (pinfunction "SP1_32") (pintype "bidirectional"))
      (node (ref "IC1") (pin "EXP@1") (pinfunction "POWERPAD_EXP@1") (pintype "bidirectional"))
      (node (ref "IC1") (pin "EXP@2") (pinfunction "POWERPAD_EXP@2") (pintype "bidirectional"))
      (node (ref "IC2") (pin "4") (pinfunction "V-_4") (pintype "bidirectional"))
      (node (ref "IC3") (pin "2") (pinfunction "VSS_2") (pintype "power_in"))
      (node (ref "IC3") (pin "5") (pinfunction "C2_5") (pintype "input"))
      (node (ref "IC5") (pin "2") (pinfunction "GND_2") (pintype "bidirectional"))
      (node (ref "IC5") (pin "TH") (pinfunction "GND_TH") (pintype "bidirectional"))
      (node (ref "ICN") (pin "1") (pinfunction "REF_1") (pintype "bidirectional"))
      (node (ref "ICN") (pin "2") (pinfunction "GND_2") (pintype "power_in"))
      (node (ref "JP1") (pin "1") (pinfunction "1_1") (pintype "passive"))
      (node (ref "JP1") (pin "2") (pinfunction "2_2") (pintype "passive"))
      (node (ref "JP2") (pin "1") (pinfunction "1_1") (pintype "passive"))
      (node (ref "JP3") (pin "1") (pinfunction "1_1") (pintype "passive"))
      (node (ref "JP4") (pin "1") (pinfunction "1_1") (pintype "passive"))
      (node (ref "JP4") (pin "3") (pinfunction "3_3") (pintype "passive"))
      (node (ref "JP5") (pin "1") (pinfunction "1_1") (pintype "passive"))
      (node (ref "JP5") (pin "3") (pinfunction "3_3") (pintype "passive"))
      (node (ref "JP6") (pin "1") (pinfunction "1_1") (pintype "passive"))
      (node (ref "JP6") (pin "3") (pinfunction "3_3") (pintype "passive"))
      (node (ref "JP7") (pin "1") (pinfunction "1_1") (pintype "passive"))
      (node (ref "JP7") (pin "3") (pinfunction "3_3") (pintype "passive"))
      (node (ref "JP7") (pin "5") (pinfunction "5_5") (pintype "passive"))
      (node (ref "JP8") (pin "1") (pinfunction "1_1") (pintype "passive"))
      (node (ref "M1") (pin "GND") (pinfunction "GND_GND") (pintype "power_in"))
      (node (ref "M1") (pin "GND1") (pinfunction "GND1_GND1") (pintype "power_in"))
      (node (ref "M1") (pin "GND2") (pinfunction "GND2_GND2") (pintype "power_in"))
      (node (ref "M2") (pin "GND") (pinfunction "GND_GND") (pintype "power_in"))
      (node (ref "PAD4") (pin "1") (pinfunction "P_1") (pintype "passive"))
      (node (ref "Q1") (pin "3") (pinfunction "D_3") (pintype "passive"))
      (node (ref "Q2") (pin "3") (pinfunction "D_3") (pintype "passive"))
      (node (ref "R1") (pin "1") (pinfunction "1_1") (pintype "passive"))
      (node (ref "R13") (pin "1") (pinfunction "1_1") (pintype "passive"))
      (node (ref "R14") (pin "1") (pinfunction "1_1") (pintype "passive"))
      (node (ref "R15") (pin "1") (pinfunction "1_1") (pintype "passive"))
      (node (ref "R16") (pin "1") (pinfunction "1_1") (pintype "passive"))
      (node (ref "R17") (pin "1") (pinfunction "1_1") (pintype "passive"))
      (node (ref "R18") (pin "1") (pinfunction "1_1") (pintype "passive"))
      (node (ref "R20") (pin "1") (pinfunction "1_1") (pintype "passive"))
      (node (ref "R24") (pin "2") (pinfunction "2_2") (pintype "passive"))
      (node (ref "R25") (pin "1") (pinfunction "1_1") (pintype "passive"))
      (node (ref "R27") (pin "2") (pinfunction "2_2") (pintype "passive"))
      (node (ref "R29") (pin "1") (pinfunction "1_1") (pintype "passive"))
      (node (ref "R39") (pin "1") (pinfunction "1_1") (pintype "passive"))
      (node (ref "R4") (pin "2") (pinfunction "2_2") (pintype "passive"))
      (node (ref "R5") (pin "1") (pinfunction "1_1") (pintype "passive"))
      (node (ref "R6") (pin "1") (pinfunction "1_1") (pintype "passive"))
      (node (ref "R7") (pin "1") (pinfunction "1_1") (pintype "passive"))
      (node (ref "S2") (pin "1") (pinfunction "O_1") (pintype "passive"))
      (node (ref "SJ7") (pin "1") (pinfunction "1_1") (pintype "passive"))
      (node (ref "SJ8") (pin "1") (pinfunction "1_1") (pintype "passive"))
    )
    (net (code "33") (name "I_BATT") (class "Default")
      (node (ref "ICN") (pin "4") (pinfunction "+IN_4") (pintype "input"))
      (node (ref "Q3") (pin "3") (pinfunction "D_3") (pintype "passive"))
      (node (ref "R26") (pin "2") (pinfunction "2_2") (pintype "passive"))
      (node (ref "R30") (pin "1") (pinfunction "1_1") (pintype "passive"))
    )
    (net (code "34") (name "NR") (class "Default")
      (node (ref "M2") (pin "NR") (pinfunction "NR_NR") (pintype "power_in"))
    )
    (net (code "35") (name "Net-(C2-Pad1)") (class "Default")
      (node (ref "C2") (pin "1") (pinfunction "1_1") (pintype "passive"))
      (node (ref "R2") (pin "1") (pinfunction "1_1") (pintype "passive"))
    )
    (net (code "36") (name "Net-(C20-Pad1)") (class "Default")
      (node (ref "C20") (pin "1") (pinfunction "1_1") (pintype "passive"))
      (node (ref "R12") (pin "1") (pinfunction "1_1") (pintype "passive"))
    )
    (net (code "37") (name "Net-(IC1-AVDD)") (class "Default")
      (node (ref "C6") (pin "2") (pinfunction "2_2") (pintype "passive"))
      (node (ref "IC1") (pin "27") (pinfunction "AVDD_27") (pintype "bidirectional"))
    )
    (net (code "38") (name "Net-(IC1-COMP)") (class "Default")
      (node (ref "C1") (pin "1") (pinfunction "1_1") (pintype "passive"))
      (node (ref "IC1") (pin "2") (pinfunction "COMP_2") (pintype "bidirectional"))
      (node (ref "R2") (pin "2") (pinfunction "2_2") (pintype "passive"))
    )
    (net (code "39") (name "Net-(IC1-CP1)") (class "Default")
      (node (ref "C4") (pin "2") (pinfunction "2_2") (pintype "passive"))
      (node (ref "IC1") (pin "14") (pinfunction "CP1_14") (pintype "bidirectional"))
    )
    (net (code "40") (name "Net-(IC1-CP2)") (class "Default")
      (node (ref "C4") (pin "1") (pinfunction "1_1") (pintype "passive"))
      (node (ref "IC1") (pin "15") (pinfunction "CP2_15") (pintype "bidirectional"))
    )
    (net (code "41") (name "Net-(IC1-DC_CAL)") (class "Default")
      (node (ref "IC1") (pin "12") (pinfunction "DC_CAL_12") (pintype "bidirectional"))
      (node (ref "R7") (pin "2") (pinfunction "2_2") (pintype "passive"))
    )
    (net (code "42") (name "Net-(IC1-DTC)") (class "Default")
      (node (ref "IC1") (pin "7") (pinfunction "DTC_7") (pintype "bidirectional"))
      (node (ref "R6") (pin "2") (pinfunction "2_2") (pintype "passive"))
    )
    (net (code "43") (name "Net-(IC1-DVDD)") (class "Default")
      (node (ref "C5") (pin "2") (pinfunction "2_2") (pintype "passive"))
      (node (ref "IC1") (pin "23") (pinfunction "DVDD_23") (pintype "bidirectional"))
    )
    (net (code "44") (name "Net-(IC1-GVDD)") (class "Default")
      (node (ref "C3") (pin "1") (pinfunction "1_1") (pintype "passive"))
      (node (ref "IC1") (pin "13") (pinfunction "GVDD_13") (pintype "bidirectional"))
    )
    (net (code "45") (name "Net-(IC1-PWRGD)") (class "Default")
      (node (ref "IC1") (pin "4") (pinfunction "PWRGD_4") (pintype "bidirectional"))
      (node (ref "R5") (pin "2") (pinfunction "2_2") (pintype "passive"))
    )
    (net (code "46") (name "Net-(IC1-RT_CLK)") (class "Default")
      (node (ref "IC1") (pin "1") (pinfunction "RT_CLK_1") (pintype "bidirectional"))
      (node (ref "R1") (pin "2") (pinfunction "2_2") (pintype "passive"))
    )
    (net (code "47") (name "Net-(IC1-SS_TR)") (class "Default")
      (node (ref "C7") (pin "1") (pinfunction "1_1") (pintype "passive"))
      (node (ref "IC1") (pin "56") (pinfunction "SS_TR_56") (pintype "bidirectional"))
    )
    (net (code "48") (name "Net-(IC1-VSENSE)") (class "Default")
      (node (ref "IC1") (pin "3") (pinfunction "VSENSE_3") (pintype "bidirectional"))
      (node (ref "R3") (pin "2") (pinfunction "2_2") (pintype "passive"))
      (node (ref "R4") (pin "1") (pinfunction "1_1") (pintype "passive"))
    )
    (net (code "49") (name "Net-(IC2-A+)") (class "Default")
      (node (ref "IC2") (pin "3") (pinfunction "A+_3") (pintype "bidirectional"))
      (node (ref "R21") (pin "2") (pinfunction "2_2") (pintype "passive"))
      (node (ref "R24") (pin "1") (pinfunction "1_1") (pintype "passive"))
    )
    (net (code "50") (name "Net-(IC2-A-)") (class "Default")
      (node (ref "IC2") (pin "2") (pinfunction "A-_2") (pintype "bidirectional"))
      (node (ref "R22") (pin "1") (pinfunction "1_1") (pintype "passive"))
      (node (ref "R23") (pin "2") (pinfunction "2_2") (pintype "passive"))
    )
    (net (code "51") (name "Net-(IC2-B+)") (class "Default")
      (node (ref "IC2") (pin "8") (pinfunction "B+_8") (pintype "bidirectional"))
      (node (ref "R19") (pin "1") (pinfunction "1_1") (pintype "passive"))
      (node (ref "R20") (pin "2") (pinfunction "2_2") (pintype "passive"))
    )
    (net (code "52") (name "Net-(IC2-B-)") (class "Default")
      (node (ref "C27") (pin "1") (pinfunction "1_1") (pintype "passive"))
      (node (ref "IC2") (pin "6") (pinfunction "B_O_6") (pintype "bidirectional"))
      (node (ref "IC2") (pin "7") (pinfunction "B-_7") (pintype "bidirectional"))
      (node (ref "R21") (pin "1") (pinfunction "1_1") (pintype "passive"))
    )
    (net (code "53") (name "Net-(IC3-PROG)") (class "Default")
      (node (ref "IC3") (pin "1") (pinfunction "PROG_1") (pintype "input"))
      (node (ref "PAD9") (pin "1") (pinfunction "P_1") (pintype "passive"))
    )
    (net (code "54") (name "Net-(IC5-EN3)") (class "Default")
      (node (ref "IC5") (pin "4") (pinfunction "EN5_4") (pintype "bidirectional"))
      (node (ref "IC5") (pin "5") (pinfunction "EN3_5") (pintype "power_in"))
      (node (ref "R27") (pin "1") (pinfunction "1_1") (pintype "passive"))
      (node (ref "R28") (pin "2") (pinfunction "2_2") (pintype "passive"))
    )
    (net (code "55") (name "Net-(IC5-V3IN)") (class "Default")
      (node (ref "IC5") (pin "6") (pinfunction "V3IN_6") (pintype "input"))
      (node (ref "SJ8") (pin "2") (pinfunction "2_2") (pintype "passive"))
    )
    (net (code "56") (name "Net-(IC5-V5IN)") (class "Default")
      (node (ref "IC5") (pin "10") (pinfunction "V5IN_10") (pintype "output"))
      (node (ref "SJ7") (pin "2") (pinfunction "2_2") (pintype "passive"))
    )
    (net (code "57") (name "Net-(ICNB-OUT)") (class "Default")
      (node (ref "ICN") (pin "6") (pinfunction "OUT_6") (pintype "output"))
      (node (ref "R38") (pin "2") (pinfunction "2_2") (pintype "passive"))
    )
    (net (code "58") (name "Net-(JP2-Pad2)") (class "Default")
      (node (ref "JP2") (pin "2") (pinfunction "2_2") (pintype "passive"))
      (node (ref "SJ7") (pin "3") (pinfunction "3_3") (pintype "passive"))
    )
    (net (code "59") (name "Net-(JP3-Pad2)") (class "Default")
      (node (ref "JP3") (pin "2") (pinfunction "2_2") (pintype "passive"))
      (node (ref "SJ8") (pin "3") (pinfunction "3_3") (pintype "passive"))
    )
    (net (code "60") (name "Net-(LED1-PadC)") (class "Default")
      (node (ref "LED1") (pin "C") (pinfunction "C_C") (pintype "passive"))
      (node (ref "R10") (pin "2") (pinfunction "2_2") (pintype "passive"))
    )
    (net (code "61") (name "Net-(LED2-PadC)") (class "Default")
      (node (ref "LED2") (pin "C") (pinfunction "C_C") (pintype "passive"))
      (node (ref "R11") (pin "2") (pinfunction "2_2") (pintype "passive"))
    )
    (net (code "62") (name "Net-(LED3-PadC)") (class "Default")
      (node (ref "LED3") (pin "C") (pinfunction "C_C") (pintype "passive"))
      (node (ref "R15") (pin "2") (pinfunction "2_2") (pintype "passive"))
    )
    (net (code "63") (name "Net-(LED4-PadC)") (class "Default")
      (node (ref "LED4") (pin "C") (pinfunction "C_C") (pintype "passive"))
      (node (ref "R14") (pin "2") (pinfunction "2_2") (pintype "passive"))
    )
    (net (code "64") (name "Net-(LED5-PadC)") (class "Default")
      (node (ref "LED5") (pin "C") (pinfunction "C_C") (pintype "passive"))
      (node (ref "R25") (pin "2") (pinfunction "2_2") (pintype "passive"))
    )
    (net (code "65") (name "Net-(Q1-S)") (class "Default")
      (node (ref "Q1") (pin "2") (pinfunction "S_2") (pintype "passive"))
      (node (ref "R10") (pin "1") (pinfunction "1_1") (pintype "passive"))
    )
    (net (code "66") (name "Net-(Q2-S)") (class "Default")
      (node (ref "Q2") (pin "2") (pinfunction "S_2") (pintype "passive"))
      (node (ref "R11") (pin "1") (pinfunction "1_1") (pintype "passive"))
    )
    (net (code "67") (name "Net-(Q3-G)") (class "Default")
      (node (ref "Q3") (pin "1") (pinfunction "G_1") (pintype "passive"))
      (node (ref "R13") (pin "2") (pinfunction "2_2") (pintype "passive"))
    )
    (net (code "68") (name "Net-(S2B-S)") (class "Default")
      (node (ref "LED5") (pin "A") (pinfunction "A_A") (pintype "passive"))
      (node (ref "S2") (pin "4") (pinfunction "S_4") (pintype "passive"))
    )
    (net (code "69") (name "OCTW") (class "Default")
      (node (ref "IC1") (pin "5") (pinfunction "OCTW_5") (pintype "bidirectional"))
      (node (ref "Q1") (pin "1") (pinfunction "G_1") (pintype "passive"))
      (node (ref "R8") (pin "1") (pinfunction "1_1") (pintype "passive"))
    )
    (net (code "70") (name "PH") (class "Default")
      (node (ref "C11") (pin "2") (pinfunction "2_2") (pintype "passive"))
      (node (ref "D1") (pin "C") (pinfunction "C_C") (pintype "passive"))
      (node (ref "IC1") (pin "50") (pinfunction "PH1_50") (pintype "bidirectional"))
      (node (ref "IC1") (pin "51") (pinfunction "PH2_51") (pintype "bidirectional"))
      (node (ref "L1") (pin "1") (pinfunction "1_1") (pintype "passive"))
    )
    (net (code "71") (name "PWM_AH") (class "Default")
      (node (ref "IC1") (pin "17") (pinfunction "INH_A_17") (pintype "bidirectional"))
      (node (ref "M1") (pin "PTB5_D3") (pinfunction "D3_PTB5_D3") (pintype "bidirectional"))
      (node (ref "M2") (pin "P$21") (pinfunction "P21_P$21") (pintype "bidirectional"))
    )
    (net (code "72") (name "PWM_AL") (class "Default")
      (node (ref "IC1") (pin "18") (pinfunction "INL_A_18") (pintype "bidirectional"))
      (node (ref "M1") (pin "PTA12_D5") (pinfunction "D5_PTA12_D5") (pintype "bidirectional"))
      (node (ref "M2") (pin "P$22") (pinfunction "P22_P$22") (pintype "bidirectional"))
    )
    (net (code "73") (name "PWM_BH") (class "Default")
      (node (ref "IC1") (pin "19") (pinfunction "INH_B_19") (pintype "bidirectional"))
      (node (ref "M1") (pin "PTB6_D6") (pinfunction "D6_PTB6_D6") (pintype "bidirectional"))
      (node (ref "M2") (pin "P$23") (pinfunction "P23_P$23") (pintype "bidirectional"))
    )
    (net (code "74") (name "PWM_BL") (class "Default")
      (node (ref "IC1") (pin "20") (pinfunction "INL_B_20") (pintype "bidirectional"))
      (node (ref "M1") (pin "PTB7_D7") (pinfunction "D7_PTB7_D7") (pintype "bidirectional"))
      (node (ref "M2") (pin "P$24") (pinfunction "P24_P$24") (pintype "bidirectional"))
    )
    (net (code "75") (name "PWM_CH") (class "Default")
      (node (ref "IC1") (pin "21") (pinfunction "INH_C_21") (pintype "bidirectional"))
      (node (ref "M1") (pin "PTB11_D9") (pinfunction "D9_PTB11_D9") (pintype "bidirectional"))
      (node (ref "M2") (pin "P$25") (pinfunction "P25_P$25") (pintype "bidirectional"))
    )
    (net (code "76") (name "PWM_CL") (class "Default")
      (node (ref "IC1") (pin "22") (pinfunction "INL_C_22") (pintype "bidirectional"))
      (node (ref "M1") (pin "PTA_D10") (pinfunction "D10_PTA_D10") (pintype "bidirectional"))
      (node (ref "M2") (pin "P$26") (pinfunction "P26_P$26") (pintype "bidirectional"))
    )
    (net (code "77") (name "RST_05Z") (class "Default")
      (node (ref "M1") (pin "RESET") (pinfunction "/RESET_RESET") (pintype "bidirectional"))
      (node (ref "S1") (pin "3") (pinfunction "3_3") (pintype "passive"))
      (node (ref "S1") (pin "4") (pinfunction "4_4") (pintype "passive"))
    )
    (net (code "78") (name "SCL") (class "Default")
      (node (ref "JP7") (pin "4") (pinfunction "4_4") (pintype "passive"))
      (node (ref "M1") (pin "I2C_SCL_PTB3_D15") (pinfunction "D15_I2C_SCL_PTB3_D15") (pintype "bidirectional"))
      (node (ref "M2") (pin "P$10") (pinfunction "P10_P$10") (pintype "bidirectional"))
    )
    (net (code "79") (name "SDA") (class "Default")
      (node (ref "JP7") (pin "2") (pinfunction "2_2") (pintype "passive"))
      (node (ref "M1") (pin "12C_SDA_PTB4_D14") (pinfunction "D14_12C_SDA_PTB4_D14") (pintype "bidirectional"))
      (node (ref "M2") (pin "P$9") (pinfunction "P9_P$9") (pintype "bidirectional"))
    )
    (net (code "80") (name "SENSE_I_BATT") (class "Default")
      (node (ref "C37") (pin "1") (pinfunction "1_1") (pintype "passive"))
      (node (ref "M1") (pin "A3_PTA0") (pinfunction "A3_A3_PTA0") (pintype "bidirectional"))
      (node (ref "M2") (pin "P$16") (pinfunction "P16_P$16") (pintype "bidirectional"))
      (node (ref "R38") (pin "1") (pinfunction "1_1") (pintype "passive"))
      (node (ref "R39") (pin "2") (pinfunction "2_2") (pintype "passive"))
    )
    (net (code "81") (name "SENSE_V_BATT") (class "Default")
      (node (ref "C29") (pin "1") (pinfunction "1_1") (pintype "passive"))
      (node (ref "M1") (pin "A4_PTA9") (pinfunction "A4_A4_PTA9") (pintype "bidirectional"))
      (node (ref "M2") (pin "P$17") (pinfunction "P17_P$17") (pintype "bidirectional"))
      (node (ref "R26") (pin "1") (pinfunction "1_1") (pintype "passive"))
      (node (ref "R29") (pin "2") (pinfunction "2_2") (pintype "passive"))
    )
    (net (code "82") (name "SH_A") (class "Default")
      (node (ref "C9") (pin "2") (pinfunction "2_2") (pintype "passive"))
      (node (ref "IC1") (pin "46") (pinfunction "SH_A_46") (pintype "bidirectional"))
      (node (ref "PAD1") (pin "1") (pinfunction "P_1") (pintype "passive"))
      (node (ref "Q4") (pin "1") (pinfunction "S_1") (pintype "passive"))
      (node (ref "Q4") (pin "2") (pinfunction "S_2") (pintype "passive"))
      (node (ref "Q4") (pin "3") (pinfunction "S_3") (pintype "passive"))
      (node (ref "Q7") (pin "5") (pinfunction "D_5") (pintype "passive"))
      (node (ref "Q7") (pin "6") (pinfunction "D_6") (pintype "passive"))
      (node (ref "Q7") (pin "7") (pinfunction "D_7") (pintype "passive"))
      (node (ref "Q7") (pin "8") (pinfunction "D_8") (pintype "passive"))
      (node (ref "Q7") (pin "PAD") (pinfunction "D_PAD") (pintype "passive"))
    )
    (net (code "83") (name "SH_B") (class "Default")
      (node (ref "C8") (pin "2") (pinfunction "2_2") (pintype "passive"))
      (node (ref "IC1") (pin "41") (pinfunction "SH_B_41") (pintype "bidirectional"))
      (node (ref "PAD2") (pin "1") (pinfunction "P_1") (pintype "passive"))
      (node (ref "Q5") (pin "1") (pinfunction "S_1") (pintype "passive"))
      (node (ref "Q5") (pin "2") (pinfunction "S_2") (pintype "passive"))
      (node (ref "Q5") (pin "3") (pinfunction "S_3") (pintype "passive"))
      (node (ref "Q8") (pin "5") (pinfunction "D_5") (pintype "passive"))
      (node (ref "Q8") (pin "6") (pinfunction "D_6") (pintype "passive"))
      (node (ref "Q8") (pin "7") (pinfunction "D_7") (pintype "passive"))
      (node (ref "Q8") (pin "8") (pinfunction "D_8") (pintype "passive"))
      (node (ref "Q8") (pin "PAD") (pinfunction "D_PAD") (pintype "passive"))
    )
    (net (code "84") (name "SH_C") (class "Default")
      (node (ref "C10") (pin "2") (pinfunction "2_2") (pintype "passive"))
      (node (ref "IC1") (pin "36") (pinfunction "SH_C_36") (pintype "bidirectional"))
      (node (ref "PAD3") (pin "1") (pinfunction "P_1") (pintype "passive"))
      (node (ref "Q6") (pin "1") (pinfunction "S_1") (pintype "passive"))
      (node (ref "Q6") (pin "2") (pinfunction "S_2") (pintype "passive"))
      (node (ref "Q6") (pin "3") (pinfunction "S_3") (pintype "passive"))
      (node (ref "Q9") (pin "5") (pinfunction "D_5") (pintype "passive"))
      (node (ref "Q9") (pin "6") (pinfunction "D_6") (pintype "passive"))
      (node (ref "Q9") (pin "7") (pinfunction "D_7") (pintype "passive"))
      (node (ref "Q9") (pin "8") (pinfunction "D_8") (pintype "passive"))
      (node (ref "Q9") (pin "PAD") (pinfunction "D_PAD") (pintype "passive"))
    )
    (net (code "85") (name "SL_A") (class "Default")
      (node (ref "C25") (pin "1") (pinfunction "1_1") (pintype "passive"))
      (node (ref "IC1") (pin "33") (pinfunction "SN1_33") (pintype "bidirectional"))
      (node (ref "IC1") (pin "44") (pinfunction "SL_A_44") (pintype "bidirectional"))
      (node (ref "Q7") (pin "1") (pinfunction "S_1") (pintype "passive"))
      (node (ref "Q7") (pin "2") (pinfunction "S_2") (pintype "passive"))
      (node (ref "Q7") (pin "3") (pinfunction "S_3") (pintype "passive"))
      (node (ref "R16") (pin "2") (pinfunction "2_2") (pintype "passive"))
      (node (ref "SJ3") (pin "2") (pinfunction "2_2") (pintype "passive"))
      (node (ref "SJ5") (pin "2") (pinfunction "2_2") (pintype "passive"))
    )
    (net (code "86") (name "SL_B") (class "Default")
      (node (ref "C23") (pin "1") (pinfunction "1_1") (pintype "passive"))
      (node (ref "IC1") (pin "31") (pinfunction "SN2_31") (pintype "bidirectional"))
      (node (ref "IC1") (pin "39") (pinfunction "SL_B_39") (pintype "bidirectional"))
      (node (ref "Q8") (pin "1") (pinfunction "S_1") (pintype "passive"))
      (node (ref "Q8") (pin "2") (pinfunction "S_2") (pintype "passive"))
      (node (ref "Q8") (pin "3") (pinfunction "S_3") (pintype "passive"))
      (node (ref "R17") (pin "2") (pinfunction "2_2") (pintype "passive"))
      (node (ref "SJ3") (pin "1") (pinfunction "1_1") (pintype "passive"))
    )
    (net (code "87") (name "SL_C") (class "Default")
      (node (ref "C24") (pin "1") (pinfunction "1_1") (pintype "passive"))
      (node (ref "IC1") (pin "34") (pinfunction "SL_C_34") (pintype "bidirectional"))
      (node (ref "Q9") (pin "1") (pinfunction "S_1") (pintype "passive"))
      (node (ref "Q9") (pin "2") (pinfunction "S_2") (pintype "passive"))
      (node (ref "Q9") (pin "3") (pinfunction "S_3") (pintype "passive"))
      (node (ref "R18") (pin "2") (pinfunction "2_2") (pintype "passive"))
      (node (ref "R23") (pin "1") (pinfunction "1_1") (pintype "passive"))
      (node (ref "SJ5") (pin "1") (pinfunction "1_1") (pintype "passive"))
    )
    (net (code "88") (name "U") (class "Default")
      (node (ref "IC3") (pin "11") (pinfunction "U_11") (pintype "output"))
      (node (ref "JP6") (pin "5") (pinfunction "5_5") (pintype "passive"))
      (node (ref "JP8") (pin "2") (pinfunction "2_2") (pintype "passive"))
      (node (ref "M1") (pin "TX_PTB2_D0") (pinfunction "D0_TX_PTB2_D0") (pintype "bidirectional"))
      (node (ref "M2") (pin "P$30") (pinfunction "P30_P$30") (pintype "bidirectional"))
    )
    (net (code "89") (name "V") (class "Default")
      (node (ref "IC3") (pin "12") (pinfunction "V_12") (pintype "output"))
      (node (ref "JP6") (pin "4") (pinfunction "4_4") (pintype "passive"))
      (node (ref "JP8") (pin "3") (pinfunction "3_3") (pintype "passive"))
      (node (ref "M1") (pin "RX_PTB1_D1") (pinfunction "D1_RX_PTB1_D1") (pintype "bidirectional"))
      (node (ref "M2") (pin "P$29") (pinfunction "P29_P$29") (pintype "bidirectional"))
    )
    (net (code "90") (name "VB") (class "Default")
      (node (ref "M2") (pin "VB") (pinfunction "VB_VB") (pintype "power_in"))
    )
    (net (code "91") (name "V_BATT") (class "Default")
      (node (ref "C15") (pin "2") (pinfunction "2_2") (pintype "passive"))
      (node (ref "C16") (pin "2") (pinfunction "2_2") (pintype "passive"))
      (node (ref "C17") (pin "1") (pinfunction "1_1") (pintype "passive"))
      (node (ref "C18") (pin "1") (pinfunction "1_1") (pintype "passive"))
      (node (ref "C19") (pin "1") (pinfunction "1_1") (pintype "passive"))
      (node (ref "C21") (pin "1") (pinfunction "1_1") (pintype "passive"))
      (node (ref "C22") (pin "1") (pinfunction "1_1") (pintype "passive"))
      (node (ref "C30") (pin "1") (pinfunction "1_1") (pintype "passive"))
      (node (ref "IC1") (pin "29") (pinfunction "PVDD1_29") (pintype "bidirectional"))
      (node (ref "IC1") (pin "53") (pinfunction "PVDD2_1_53") (pintype "bidirectional"))
      (node (ref "IC1") (pin "54") (pinfunction "PVDD2_2_54") (pintype "bidirectional"))
      (node (ref "IC5") (pin "8") (pinfunction "VIN_8") (pintype "input"))
      (node (ref "ICN") (pin "3") (pinfunction "V+_3") (pintype "power_in"))
      (node (ref "ICN") (pin "5") (pinfunction "-IN_5") (pintype "input"))
      (node (ref "LED4") (pin "A") (pinfunction "A_A") (pintype "passive"))
      (node (ref "M1") (pin "VIN") (pinfunction "VIN_VIN") (pintype "power_in"))
      (node (ref "M2") (pin "VIN") (pinfunction "VIN_VIN") (pintype "power_in"))
      (node (ref "Q4") (pin "5") (pinfunction "D_5") (pintype "passive"))
      (node (ref "Q4") (pin "6") (pinfunction "D_6") (pintype "passive"))
      (node (ref "Q4") (pin "7") (pinfunction "D_7") (pintype "passive"))
      (node (ref "Q4") (pin "8") (pinfunction "D_8") (pintype "passive"))
      (node (ref "Q4") (pin "PAD") (pinfunction "D_PAD") (pintype "passive"))
      (node (ref "Q5") (pin "5") (pinfunction "D_5") (pintype "passive"))
      (node (ref "Q5") (pin "6") (pinfunction "D_6") (pintype "passive"))
      (node (ref "Q5") (pin "7") (pinfunction "D_7") (pintype "passive"))
      (node (ref "Q5") (pin "8") (pinfunction "D_8") (pintype "passive"))
      (node (ref "Q5") (pin "PAD") (pinfunction "D_PAD") (pintype "passive"))
      (node (ref "Q6") (pin "5") (pinfunction "D_5") (pintype "passive"))
      (node (ref "Q6") (pin "6") (pinfunction "D_6") (pintype "passive"))
      (node (ref "Q6") (pin "7") (pinfunction "D_7") (pintype "passive"))
      (node (ref "Q6") (pin "8") (pinfunction "D_8") (pintype "passive"))
      (node (ref "Q6") (pin "PAD") (pinfunction "D_PAD") (pintype "passive"))
      (node (ref "R12") (pin "2") (pinfunction "2_2") (pintype "passive"))
      (node (ref "R28") (pin "1") (pinfunction "1_1") (pintype "passive"))
      (node (ref "R30") (pin "2") (pinfunction "2_2") (pintype "passive"))
    )
    (net (code "92") (name "W") (class "Default")
      (node (ref "IC3") (pin "13") (pinfunction "W_13") (pintype "output"))
      (node (ref "JP6") (pin "2") (pinfunction "2_2") (pintype "passive"))
      (node (ref "JP8") (pin "4") (pinfunction "4_4") (pintype "passive"))
      (node (ref "M1") (pin "PTA11_D2") (pinfunction "D2_PTA11_D2") (pintype "bidirectional"))
      (node (ref "M2") (pin "P$28") (pinfunction "P28_P$28") (pintype "bidirectional"))
    )
    (net (code "93") (name "unconnected-(IC1-EN_BUCK-Pad55)") (class "Default")
      (node (ref "IC1") (pin "55") (pinfunction "EN_BUCK_55") (pintype "bidirectional"))
    )
    (net (code "94") (name "unconnected-(IC3-A-Pad14)") (class "Default")
      (node (ref "IC3") (pin "14") (pinfunction "A_14") (pintype "output"))
    )
    (net (code "95") (name "unconnected-(IC3-B-Pad15)") (class "Default")
      (node (ref "IC3") (pin "15") (pinfunction "B_15") (pintype "output"))
    )
    (net (code "96") (name "unconnected-(IC3-DX-Pad3)") (class "Default")
      (node (ref "IC3") (pin "3") (pinfunction "DX_3") (pintype "input"))
    )
    (net (code "97") (name "unconnected-(IC3-INDEX-Pad16)") (class "Default")
      (node (ref "IC3") (pin "16") (pinfunction "INDEX_16") (pintype "output"))
    )
    (net (code "98") (name "unconnected-(IC3-PWM-Pad6)") (class "Default")
      (node (ref "IC3") (pin "6") (pinfunction "PWM_6") (pintype "output"))
    )
    (net (code "99") (name "unconnected-(IC3-TB0-Pad17)") (class "Default")
      (node (ref "IC3") (pin "17") (pinfunction "TB0_17") (pintype "tri_state"))
    )
    (net (code "100") (name "unconnected-(IC3-TB1-Pad18)") (class "Default")
      (node (ref "IC3") (pin "18") (pinfunction "TB1_18") (pintype "tri_state"))
    )
    (net (code "101") (name "unconnected-(IC3-TB2-Pad19)") (class "Default")
      (node (ref "IC3") (pin "19") (pinfunction "TB2_19") (pintype "tri_state"))
    )
    (net (code "102") (name "unconnected-(IC3-TB3-Pad20)") (class "Default")
      (node (ref "IC3") (pin "20") (pinfunction "TB3_20") (pintype "tri_state"))
    )
    (net (code "103") (name "unconnected-(IC3-TESTCOIL-Pad8)") (class "Default")
      (node (ref "IC3") (pin "8") (pinfunction "TESTCOIL_8") (pintype "tri_state"))
    )
    (net (code "104") (name "unconnected-(IC5-VCLK-Pad1)") (class "Default")
      (node (ref "IC5") (pin "1") (pinfunction "VCLK_1") (pintype "input"))
    )
    (net (code "105") (name "unconnected-(IC5-VRTC3-Pad3)") (class "Default")
      (node (ref "IC5") (pin "3") (pinfunction "VRTC3_3") (pintype "bidirectional"))
    )
    (net (code "106") (name "unconnected-(M1-Pad5V)") (class "Default")
      (node (ref "M1") (pin "5V") (pinfunction "5V_5V") (pintype "output"))
    )
    (net (code "107") (name "unconnected-(M1-PadIOREF)") (class "Default")
      (node (ref "M1") (pin "IOREF") (pinfunction "IOREF_IOREF") (pintype "bidirectional"))
    )
    (net (code "108") (name "unconnected-(M1-PadSDA_PTDS)") (class "Default")
      (node (ref "M1") (pin "SDA_PTDS") (pinfunction "SDA_PTDS_SDA_PTDS") (pintype "bidirectional"))
    )
    (net (code "109") (name "unconnected-(M2-PadD+)") (class "Default")
      (node (ref "M2") (pin "D+") (pinfunction "D+_D+") (pintype "bidirectional"))
    )
    (net (code "110") (name "unconnected-(M2-PadD-)") (class "Default")
      (node (ref "M2") (pin "D-") (pinfunction "D-_D-") (pintype "bidirectional"))
    )
    (net (code "111") (name "unconnected-(M2-PadIF+)") (class "Default")
      (node (ref "M2") (pin "IF+") (pinfunction "IF+_IF+") (pintype "bidirectional"))
    )
    (net (code "112") (name "unconnected-(M2-PadIF-)") (class "Default")
      (node (ref "M2") (pin "IF-") (pinfunction "IF-_IF-") (pintype "bidirectional"))
    )
    (net (code "113") (name "unconnected-(M2-PadRD+)") (class "Default")
      (node (ref "M2") (pin "RD+") (pinfunction "RD+_RD+") (pintype "bidirectional"))
    )
    (net (code "114") (name "unconnected-(M2-PadRD-)") (class "Default")
      (node (ref "M2") (pin "RD-") (pinfunction "RD-_RD-") (pintype "bidirectional"))
    )
    (net (code "115") (name "unconnected-(M2-PadTD+)") (class "Default")
      (node (ref "M2") (pin "TD+") (pinfunction "TD+_TD+") (pintype "bidirectional"))
    )
    (net (code "116") (name "unconnected-(M2-PadTD-)") (class "Default")
      (node (ref "M2") (pin "TD-") (pinfunction "TD-_TD-") (pintype "bidirectional"))
    )
    (net (code "117") (name "unconnected-(M2-PadVU)") (class "Default")
      (node (ref "M2") (pin "VU") (pinfunction "VU_VU") (pintype "output"))
    )
    (net (code "118") (name "unconnected-(S2B-O-Pad6)") (class "Default")
      (node (ref "S2") (pin "6") (pinfunction "O_6") (pintype "passive"))
    )
  )
)
